# lune-v6-rev3_3.net
KiCad netlist of a schematic drawn in EasyEDA Pro
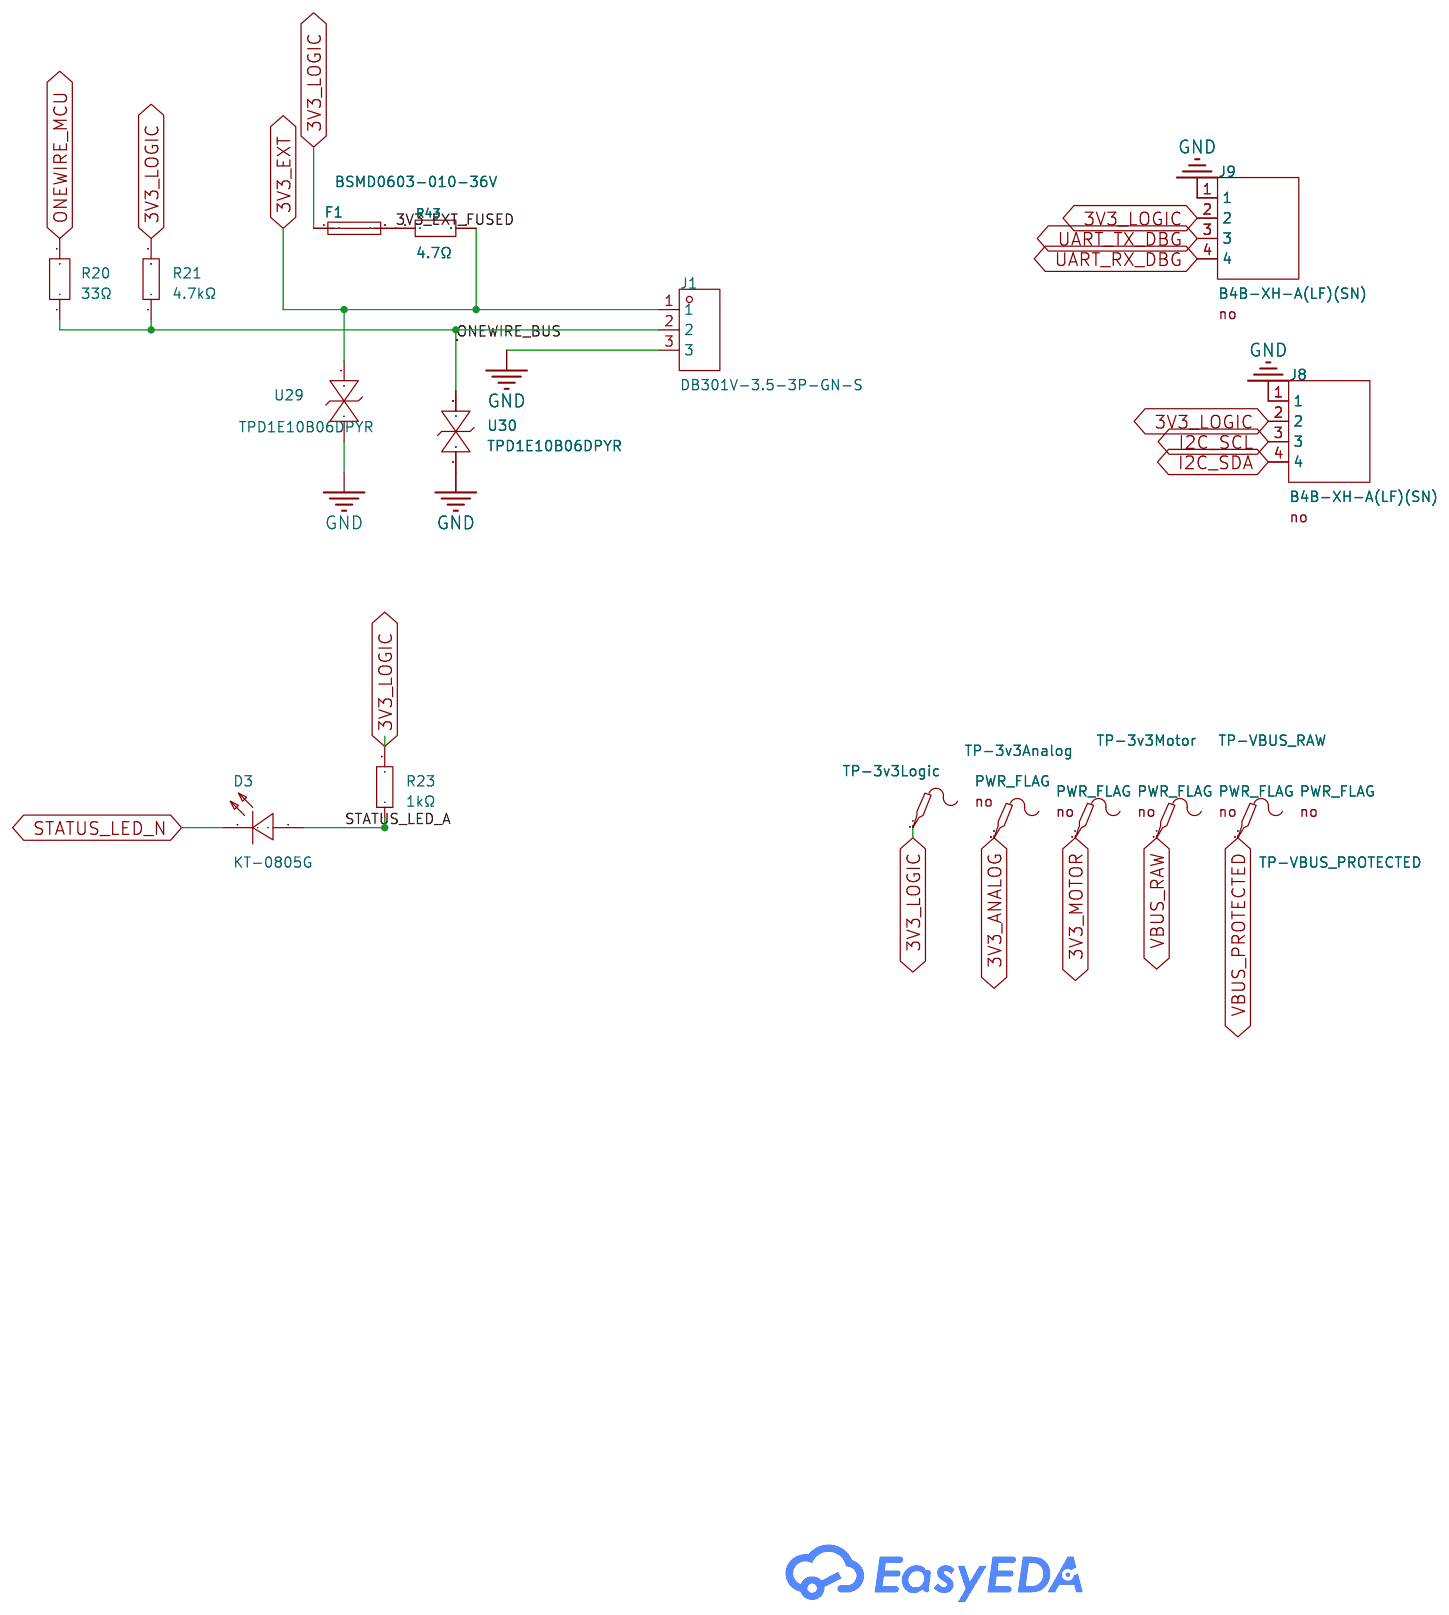
[diagram p0: Connectors]
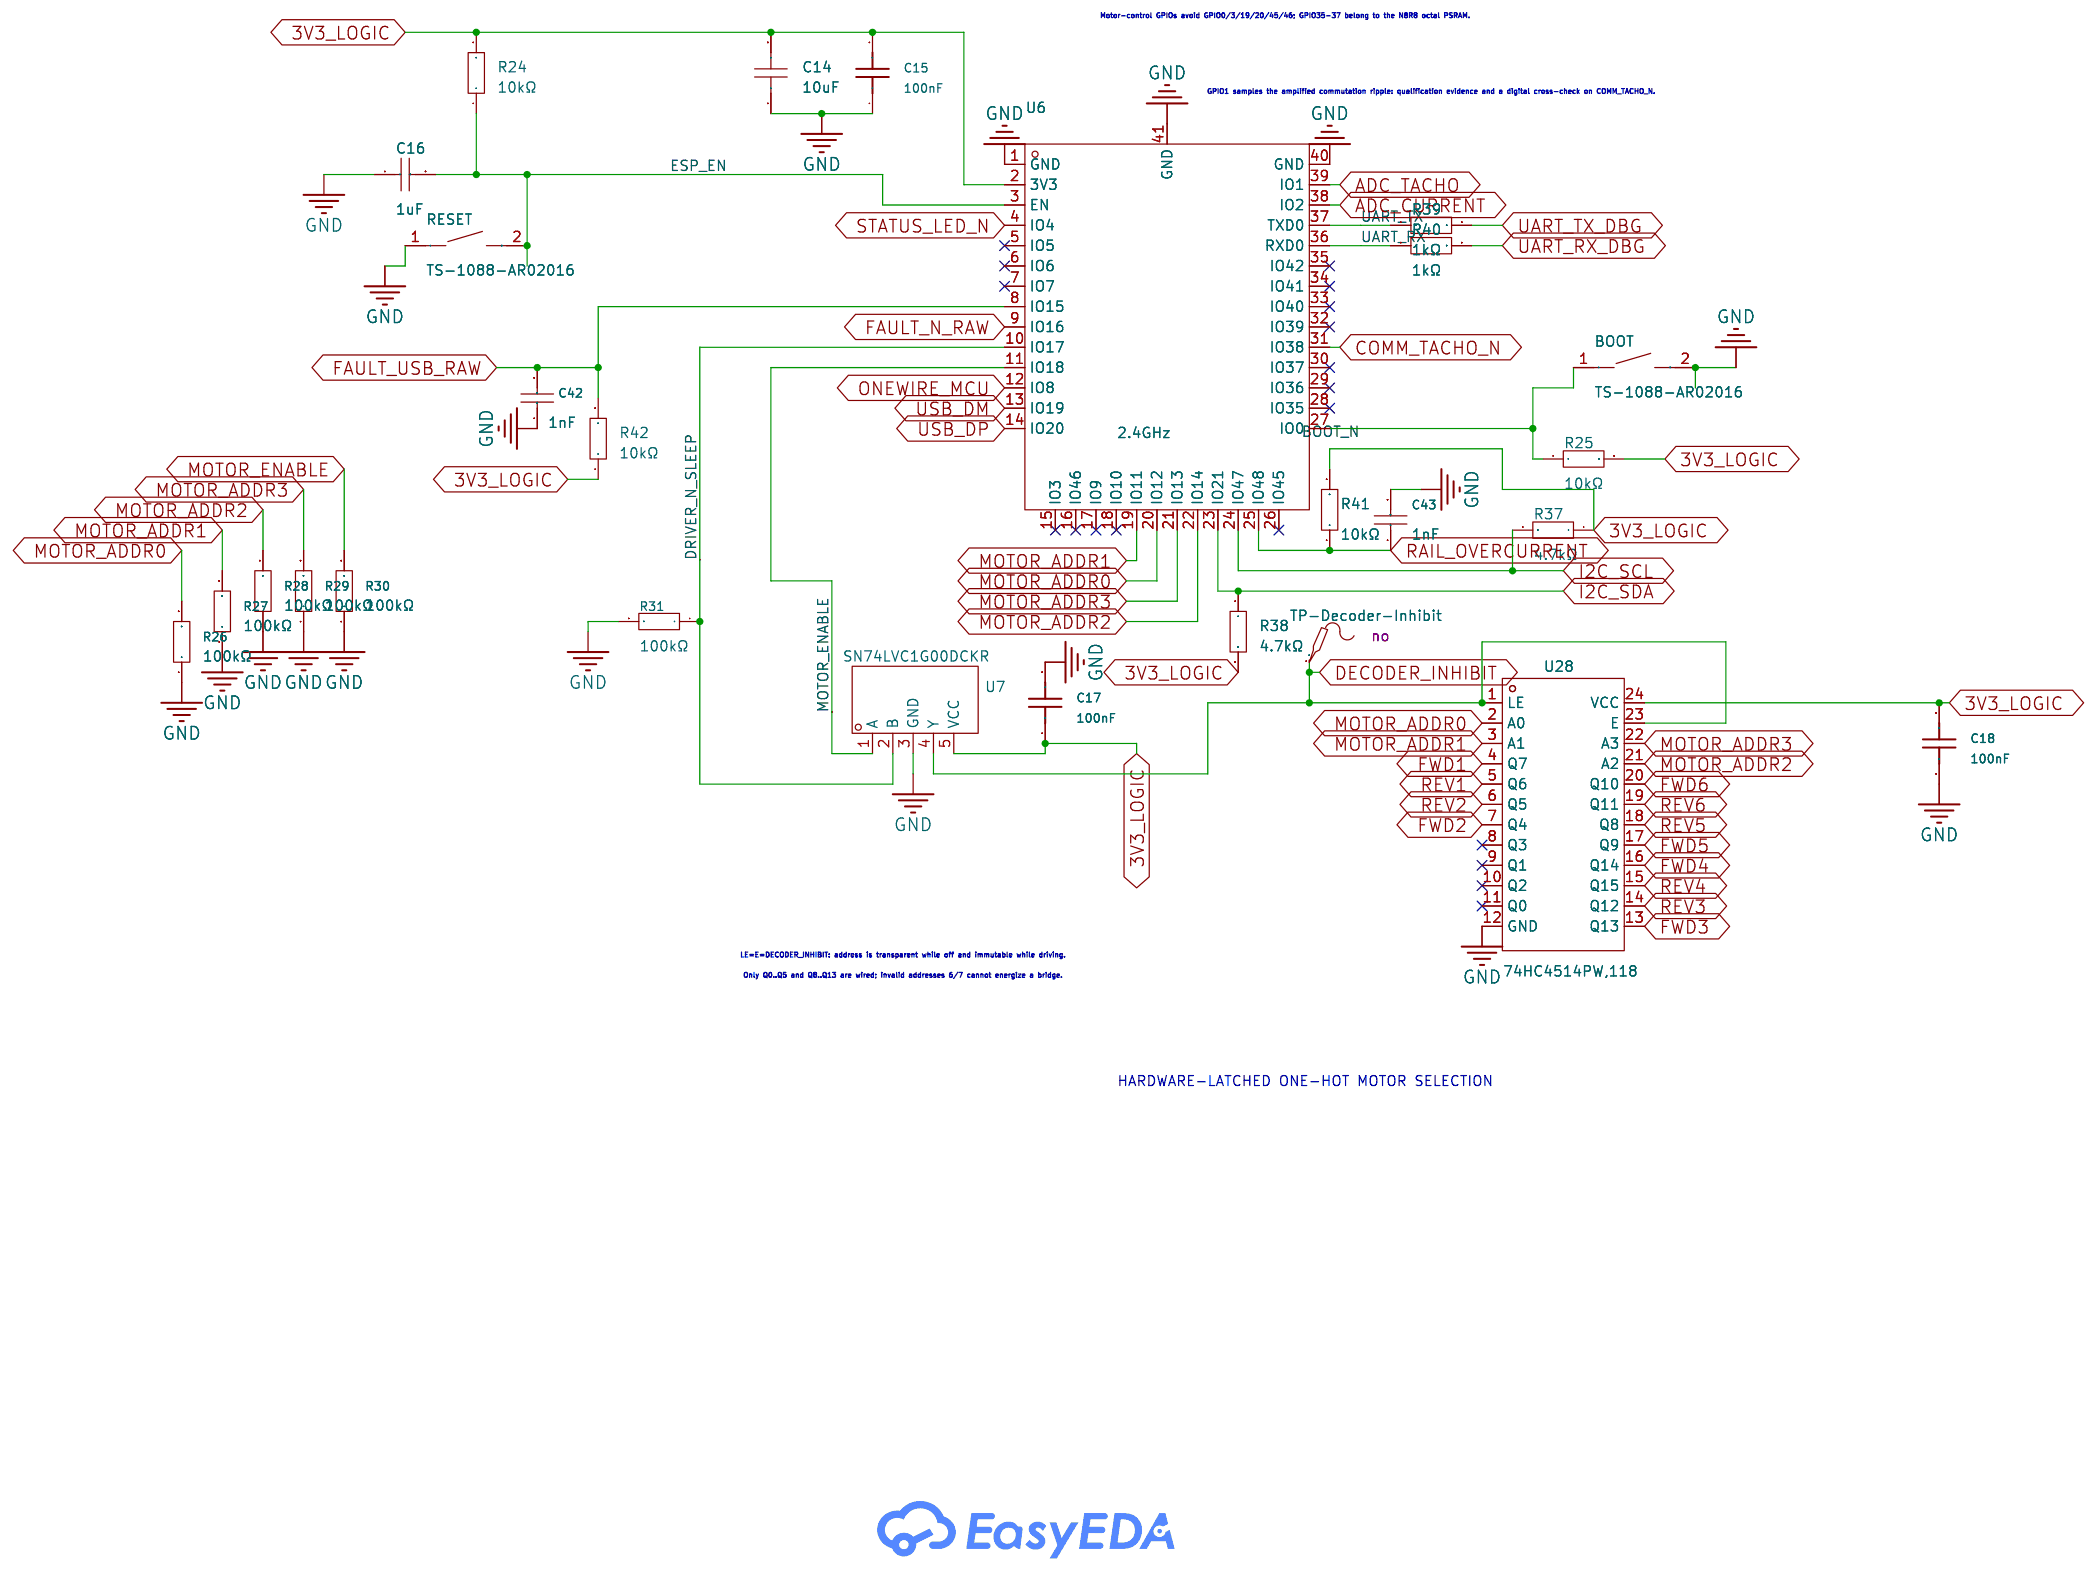
[diagram p1: Controller]
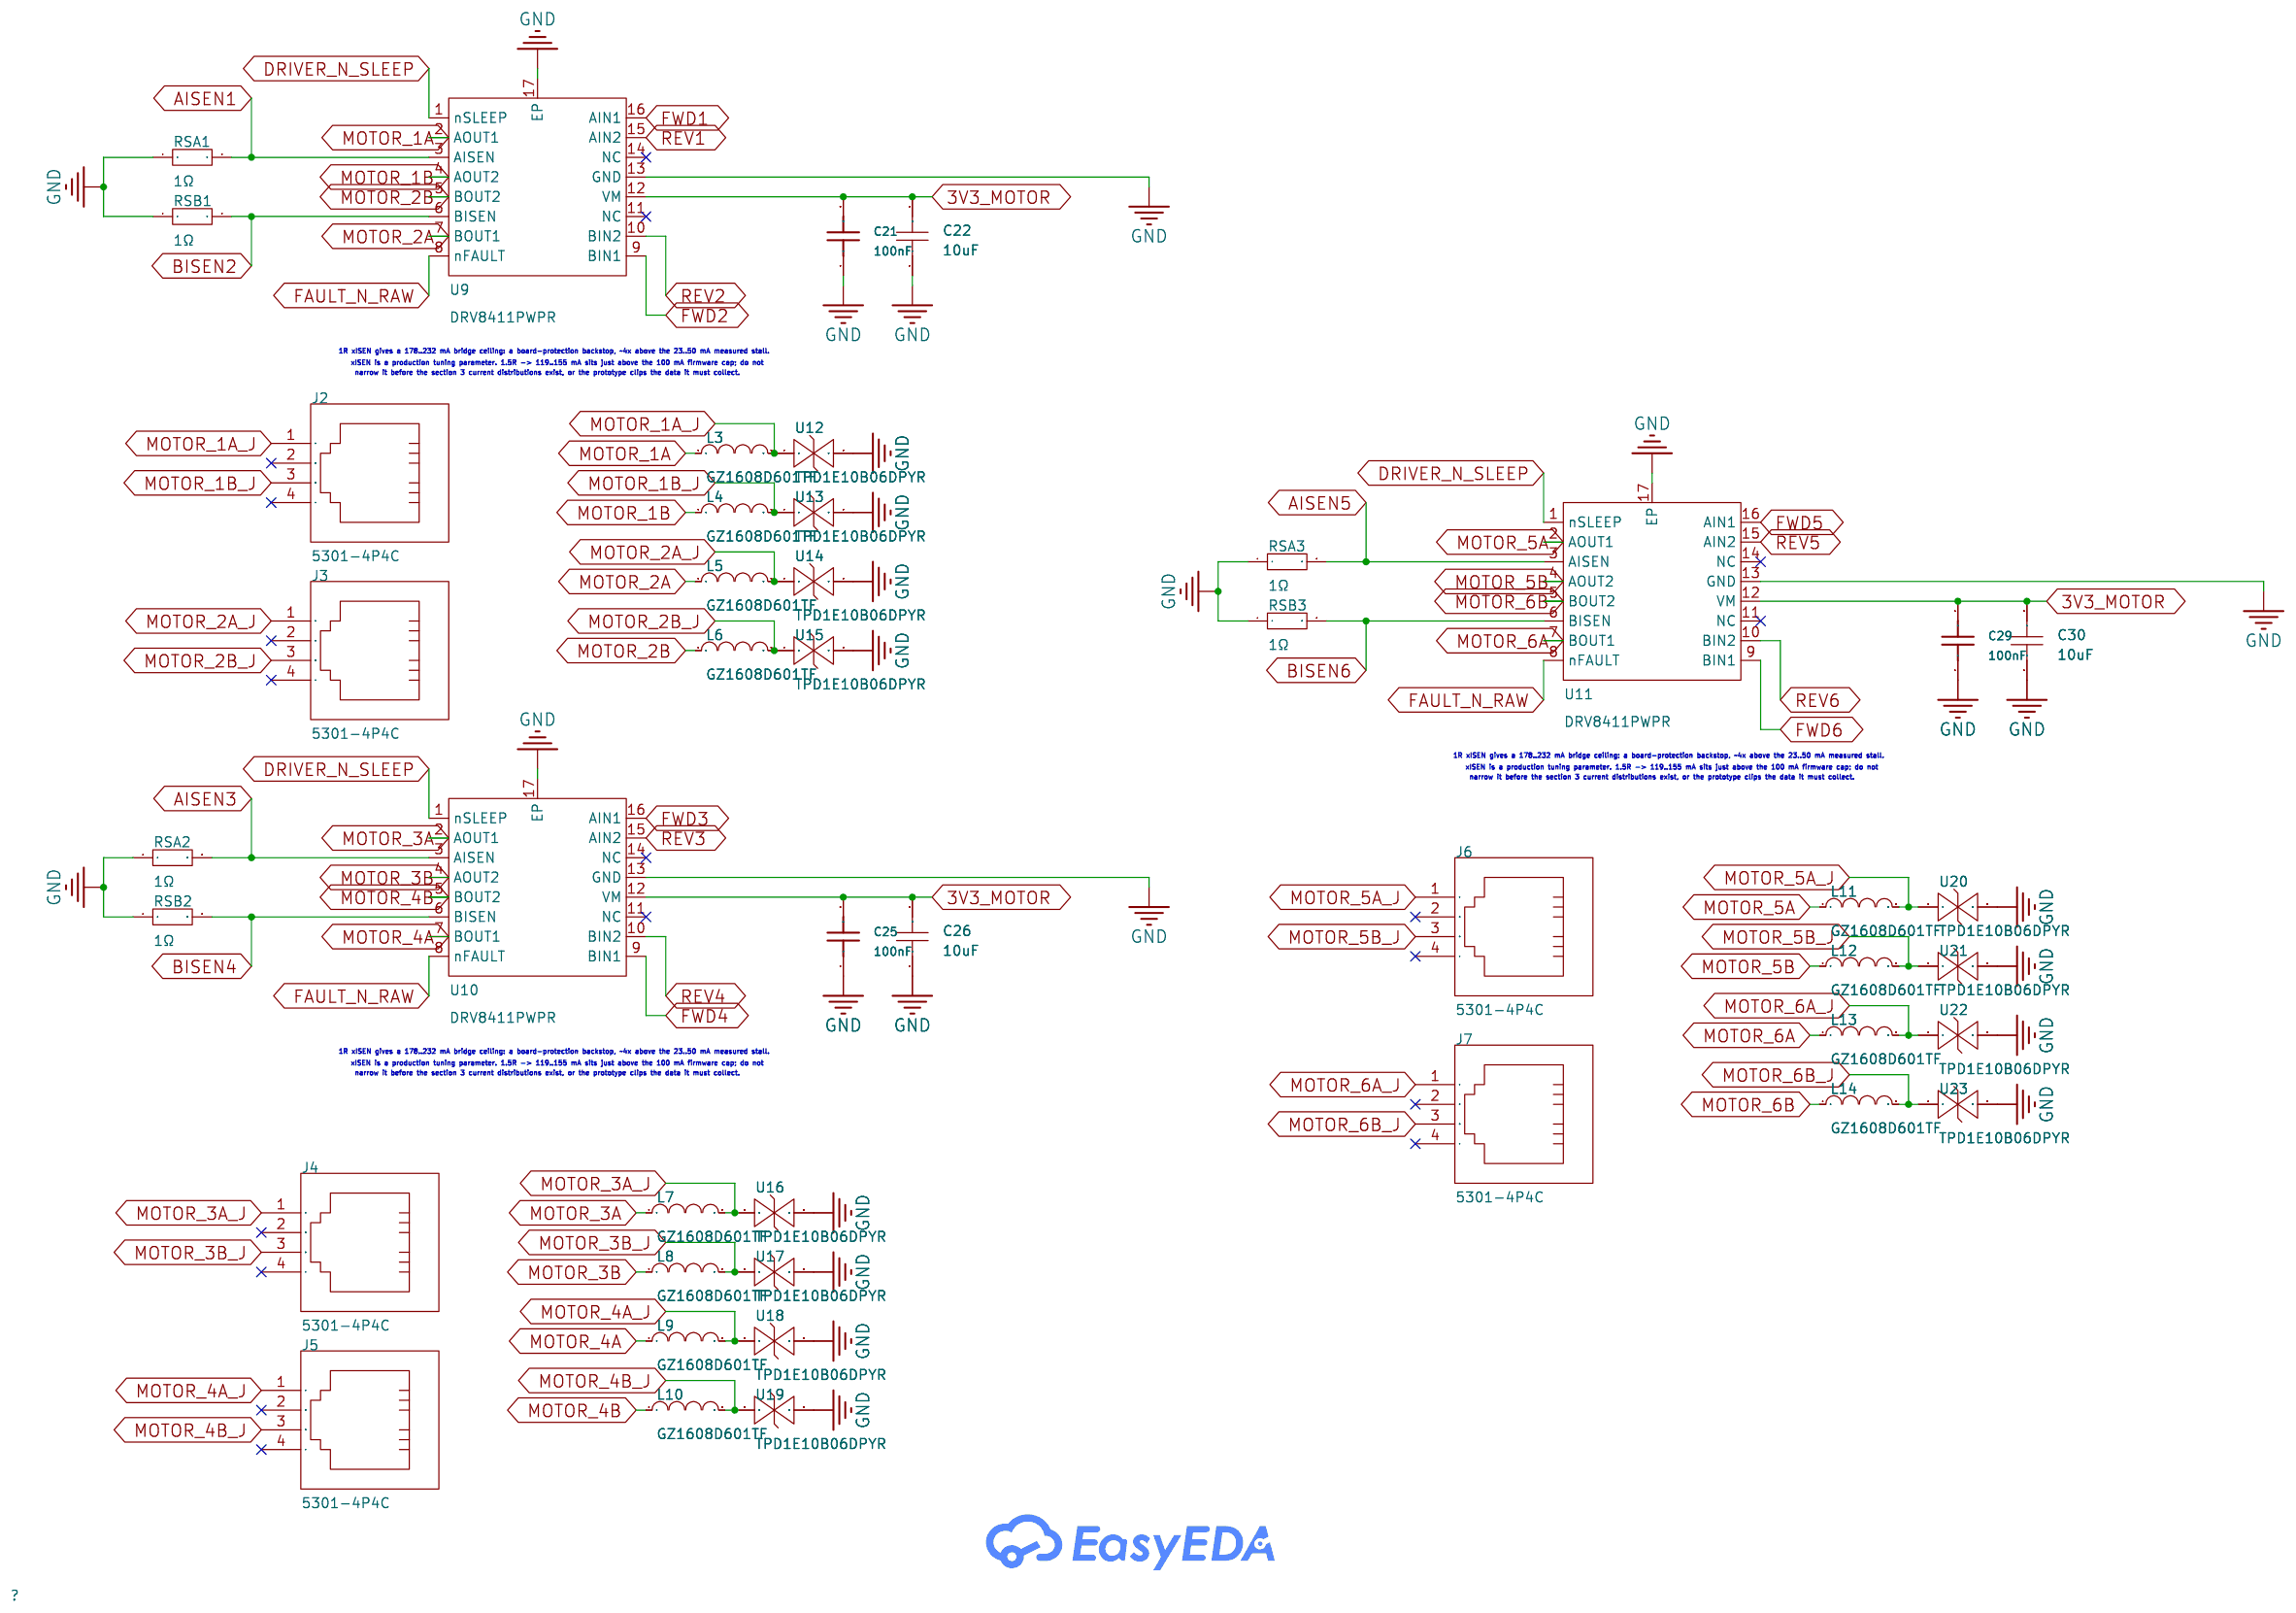
[diagram p2: Motors]
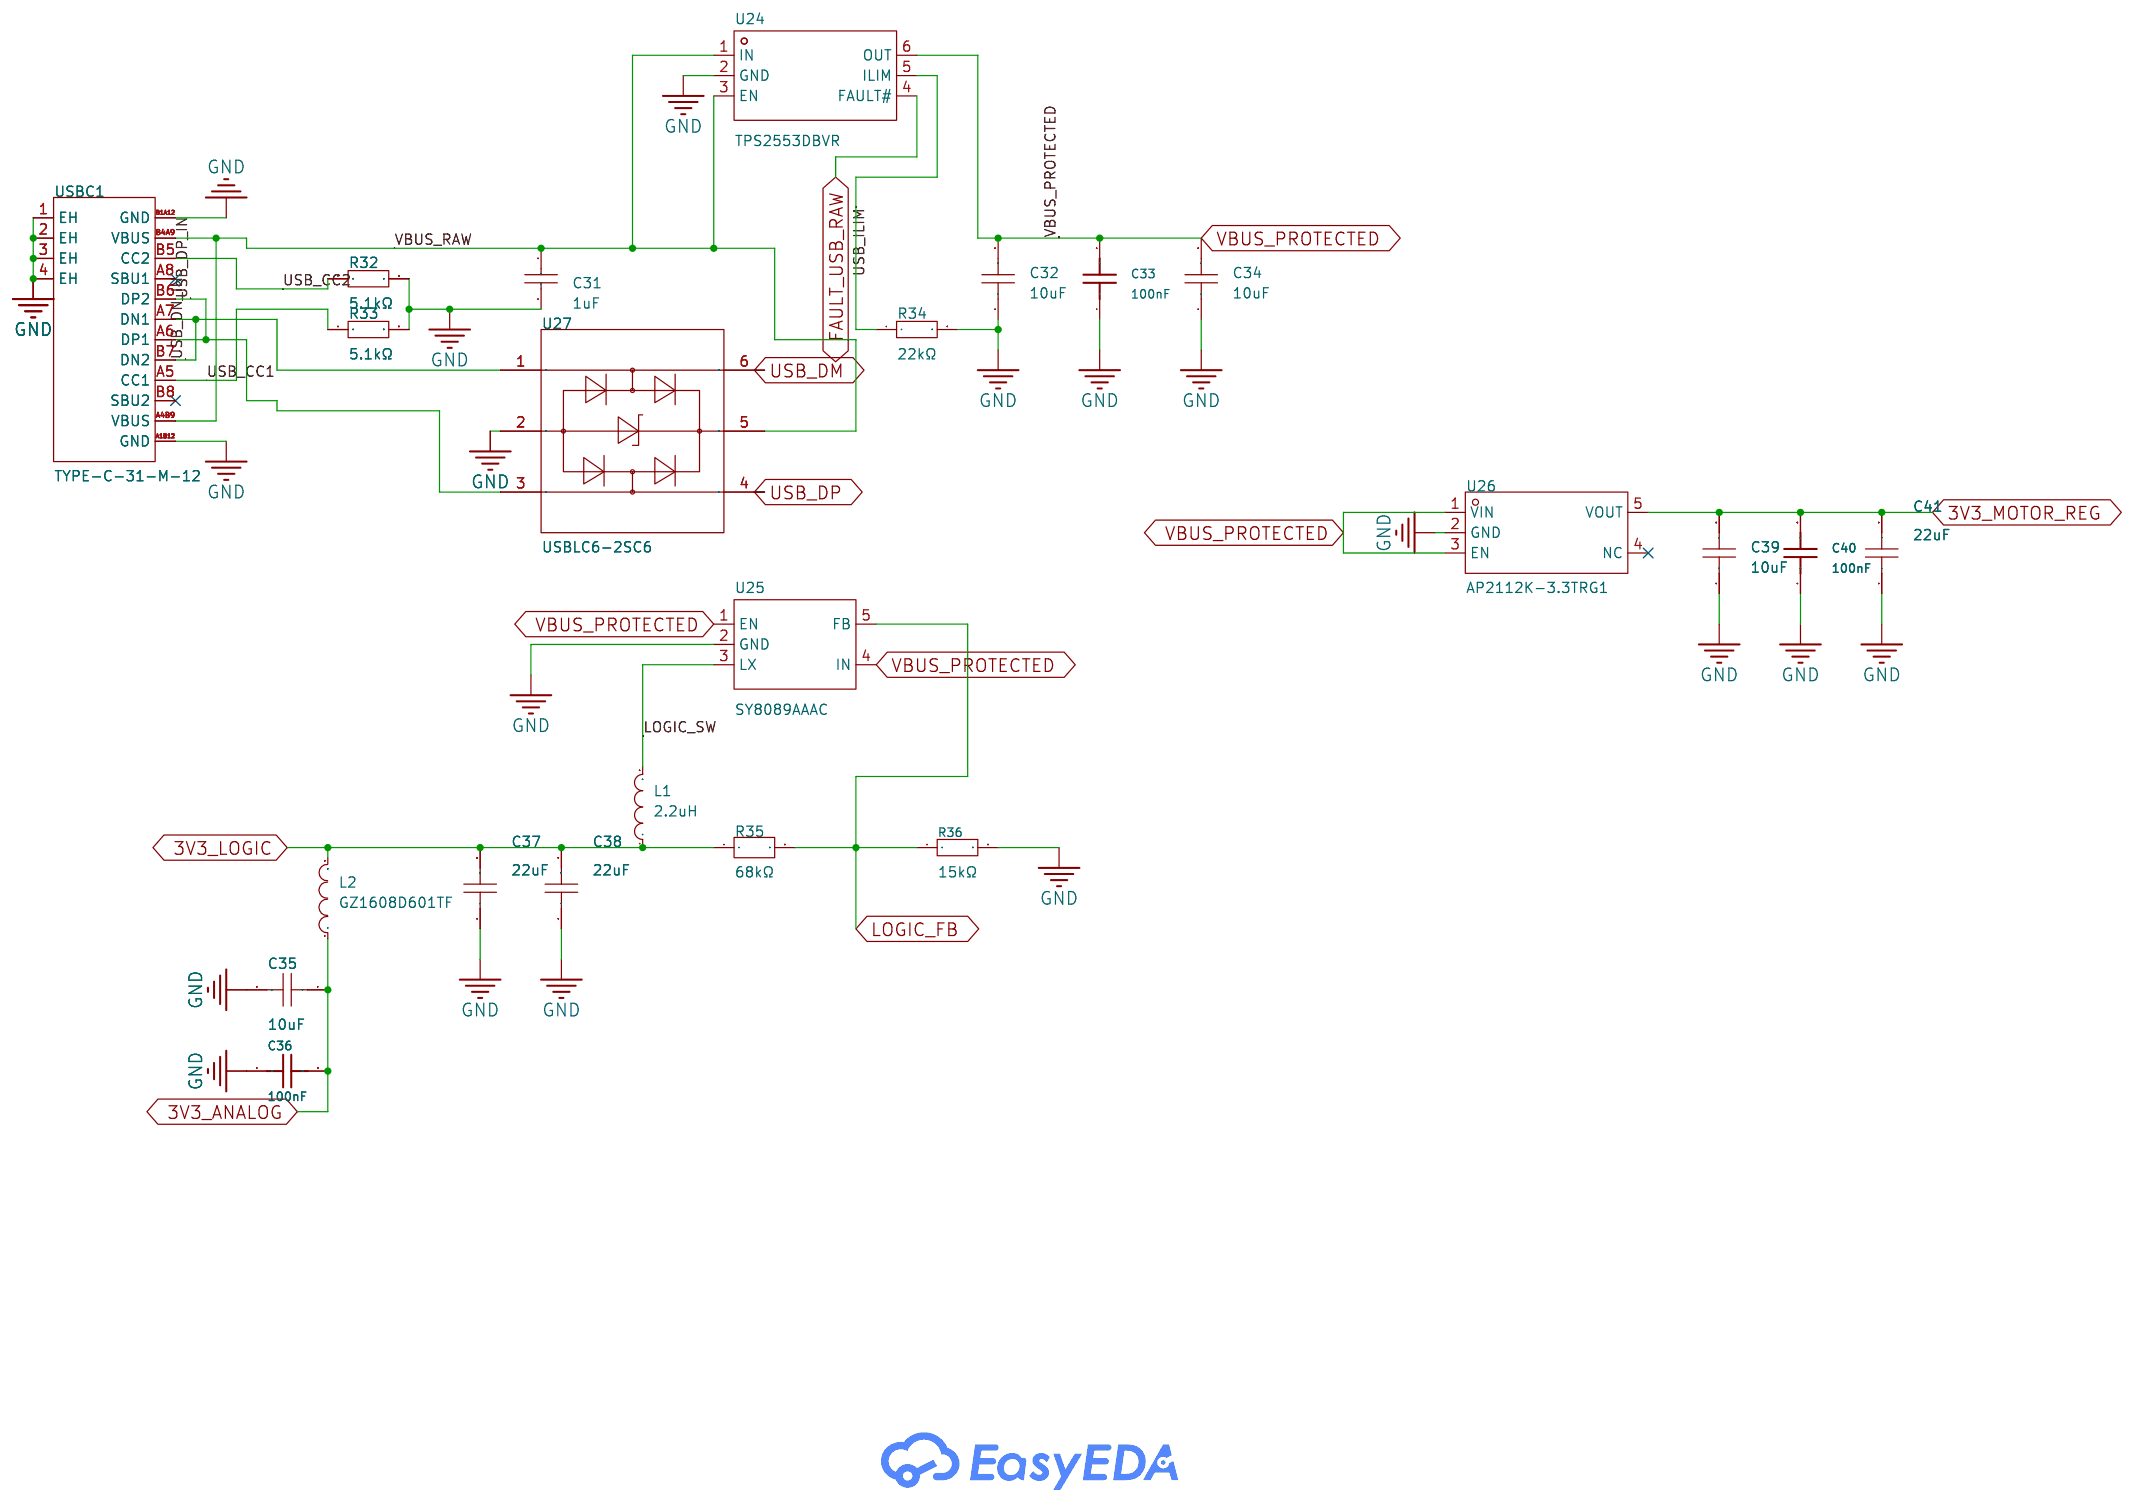
[diagram p3: Power]
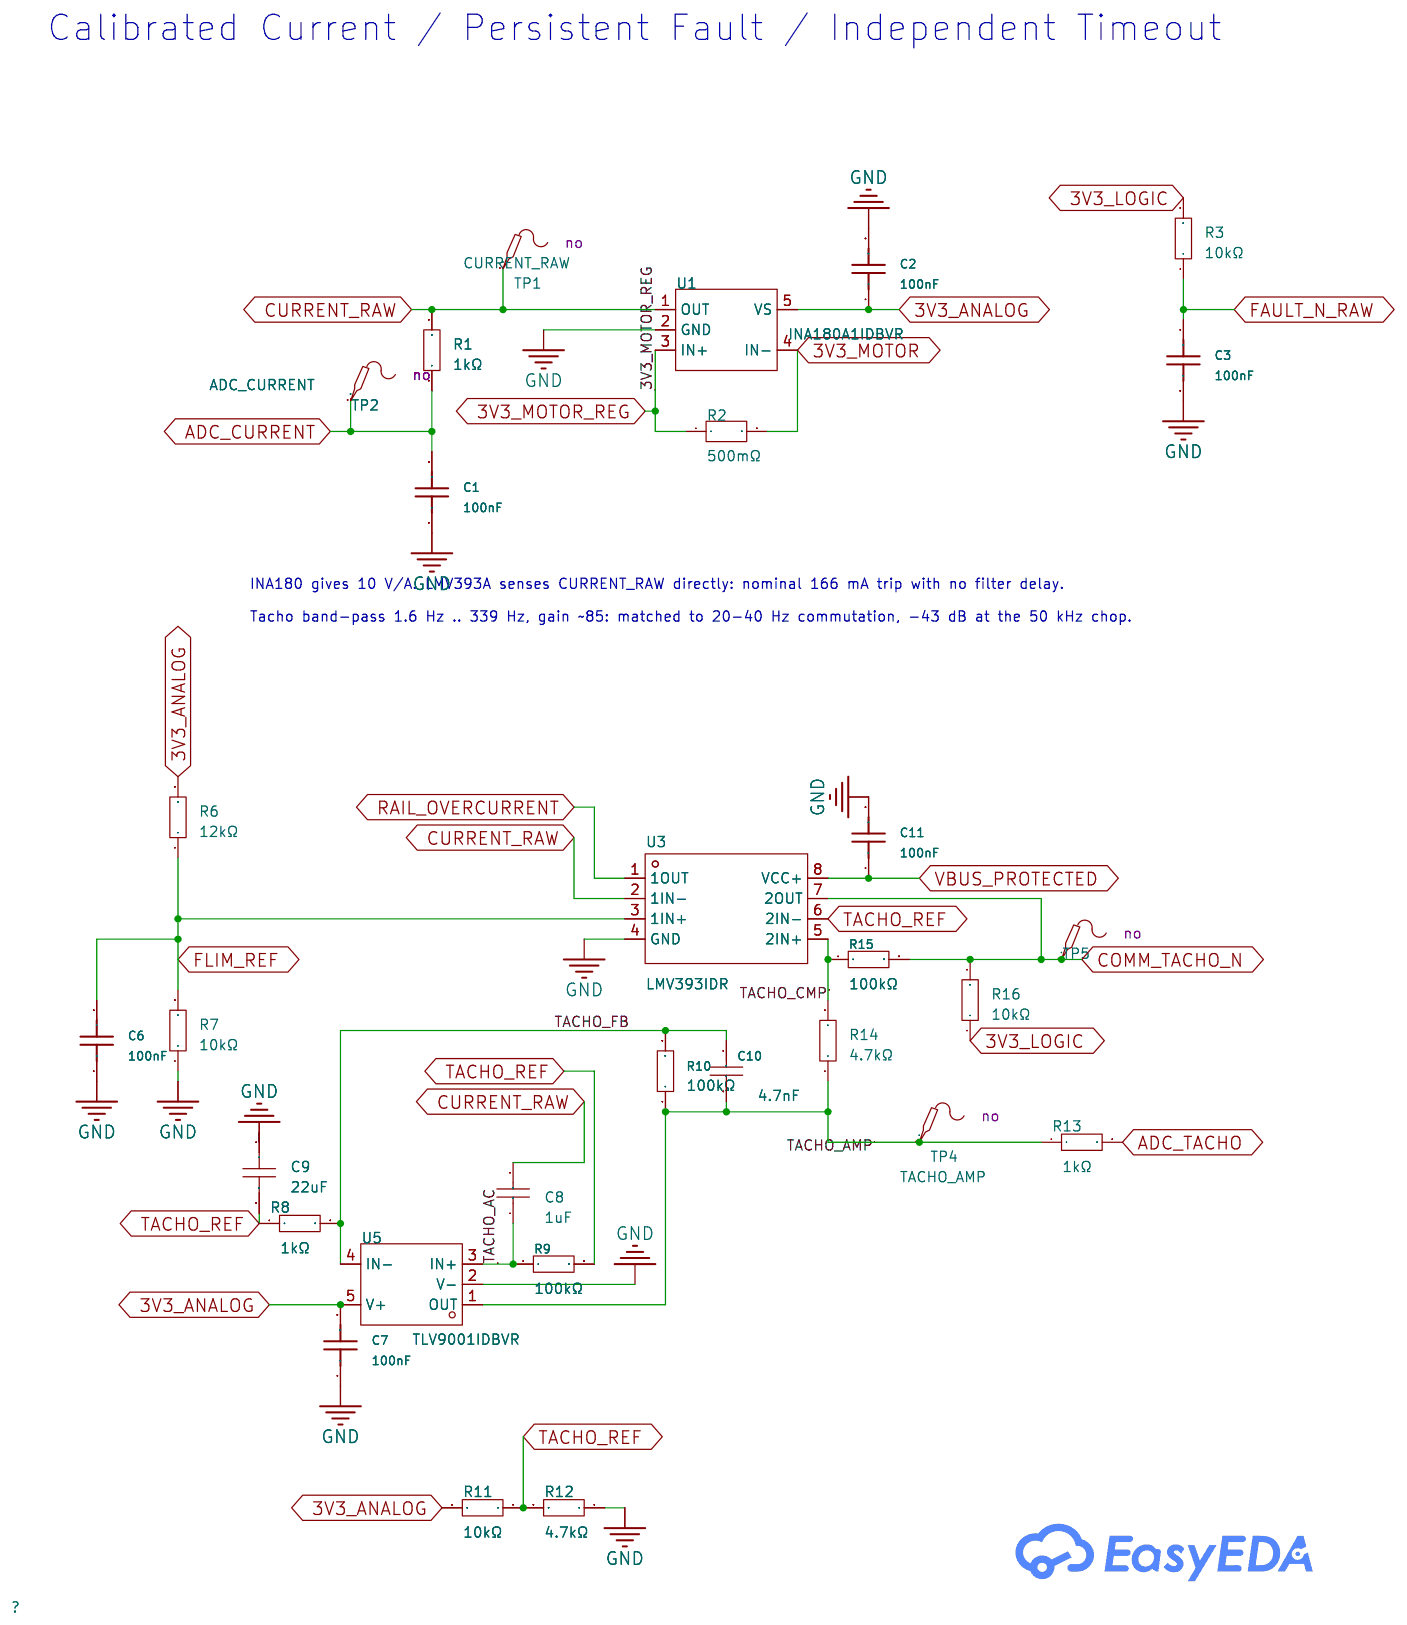
[diagram p4: Analog]

(export (version "E")
  (design (tool "Eeschema 10.0.6"))
  (components
    (comp (ref "D3")
      (value "KT-0805G")
      (footprint "easyedapro:LED0805-R-RD")
      (fields (field (name "Manufacturer") "KENTO"))
      (libsource (lib "easyedapro") (part "0805G (Green)"))
    )
    (comp (ref "F1")
      (value "BSMD0603-010-36V")
      (footprint "easyedapro:F0603")
      (fields (field (name "Manufacturer") "BHFUSE(佰宏)"))
      (libsource (lib "easyedapro") (part "BSMD0603-010-36V"))
    )
    (comp (ref "J1")
      (value "DB301V-3.5-3P-GN-S")
      (footprint "easyedapro:CONN-TH_DB301V-3.5-3P-GN")
      (fields (field (name "Manufacturer") "DORABO(地博电气)"))
      (libsource (lib "easyedapro") (part "DB301V-3.5-3P-GN"))
    )
    (comp (ref "J8")
      (value "B4B-XH-A(LF)(SN)")
      (footprint "easyedapro:CONN-TH_B4B-XH-A-LF-SN")
      (fields (field (name "Manufacturer") "JST") (field (name "Add into BOM") "no"))
      (libsource (lib "easyedapro") (part "B4B-XH-A(LF)(SN)"))
    )
    (comp (ref "J9")
      (value "B4B-XH-A(LF)(SN)")
      (footprint "easyedapro:CONN-TH_B4B-XH-A-LF-SN")
      (fields (field (name "Manufacturer") "JST") (field (name "Add into BOM") "no"))
      (libsource (lib "easyedapro") (part "B4B-XH-A(LF)(SN)"))
    )
    (comp (ref "R20")
      (value "33Ω")
      (footprint "easyedapro:R0603")
      (fields
        (field (name "Manufacturer Part") "0603WAF330JT5E")
        (field (name "Manufacturer") "UNI-ROYAL(厚声)")
      )
      (libsource (lib "easyedapro") (part "CRCW060333R0FKEA"))
    )
    (comp (ref "R21")
      (value "4.7kΩ")
      (footprint "easyedapro:R0603")
      (fields
        (field (name "Manufacturer Part") "0603WAF4701T5E")
        (field (name "Manufacturer") "UNI-ROYAL(厚声)")
      )
      (libsource (lib "easyedapro") (part "RC0603FR-074K7L"))
    )
    (comp (ref "R23")
      (value "1kΩ")
      (footprint "easyedapro:R0603")
      (fields
        (field (name "Manufacturer Part") "0603WAF1001T5E")
        (field (name "Manufacturer") "UNI-ROYAL(厚声)")
      )
      (libsource (lib "easyedapro") (part "RC0603FR-071KL"))
    )
    (comp (ref "R43")
      (value "4.7Ω")
      (footprint "easyedapro:R0603")
      (fields
        (field (name "Manufacturer Part") "0603WAF470KT5E")
        (field (name "Manufacturer") "UNI-ROYAL(厚声)")
      )
      (libsource (lib "easyedapro") (part "0603WAF470KT5E"))
    )
    (comp (ref "TP-3v3Analog")
      (value "PWR_FLAG")
      (footprint "easyedapro:Test-Point-0.5mm")
      (description "Test Point 测试点")
      (fields (field (name "Add into BOM") "no"))
      (libsource (lib "easyedapro") (part "Test-Point"))
    )
    (comp (ref "TP-3v3Logic")
      (value "PWR_FLAG")
      (footprint "easyedapro:Test-Point-0.5mm")
      (description "Test Point 测试点")
      (fields (field (name "Add into BOM") "no"))
      (libsource (lib "easyedapro") (part "Test-Point"))
    )
    (comp (ref "TP-3v3Motor")
      (value "PWR_FLAG")
      (footprint "easyedapro:Test-Point-0.5mm")
      (description "Test Point 测试点")
      (fields (field (name "Add into BOM") "no"))
      (libsource (lib "easyedapro") (part "Test-Point"))
    )
    (comp (ref "TP-VBUS_PROTECTED")
      (value "PWR_FLAG")
      (footprint "easyedapro:Test-Point-0.5mm")
      (description "Test Point 测试点")
      (fields (field (name "Add into BOM") "no"))
      (libsource (lib "easyedapro") (part "Test-Point"))
    )
    (comp (ref "TP-VBUS_RAW")
      (value "PWR_FLAG")
      (footprint "easyedapro:Test-Point-0.5mm")
      (description "Test Point 测试点")
      (fields (field (name "Add into BOM") "no"))
      (libsource (lib "easyedapro") (part "Test-Point"))
    )
    (comp (ref "U29")
      (value "TPD1E10B06DPYR")
      (footprint "easyedapro:X1SON-2_L1.0-W0.6-P0.65-BI-1")
      (fields (field (name "Manufacturer") "TI(德州仪器)"))
      (libsource (lib "easyedapro") (part "TPD1E10B06DPYR"))
    )
    (comp (ref "U30")
      (value "TPD1E10B06DPYR")
      (footprint "easyedapro:X1SON-2_L1.0-W0.6-P0.65-BI-1")
      (fields (field (name "Manufacturer") "TI(德州仪器)"))
      (libsource (lib "easyedapro") (part "TPD1E10B06DPYR"))
    )
    (comp (ref "BOOT")
      (value "TS-1088-AR02016")
      (footprint "easyedapro:SW-SMD_L3.9-W3.0-P4.45")
      (fields (field (name "Manufacturer") "XUNPU(讯普)"))
      (libsource (lib "easyedapro") (part "TS-1088-AR02016"))
    )
    (comp (ref "C14")
      (value "10uF")
      (footprint "easyedapro:C0603")
      (description "Capacitance:10uF Tolerance:±10% Tolerance:±10% Voltage Rating:16V Temperature Coefficient:X5R")
      (fields
        (field (name "Manufacturer Part") "CL10A106KP8NNNC")
        (field (name "Manufacturer") "SAMSUNG(三星)")
      )
      (libsource (lib "easyedapro") (part "TCC0603X5R106K160CT"))
    )
    (comp (ref "C15")
      (value "100nF")
      (footprint "easyedapro:C0603")
      (description "Capacitance:100nF Tolerance:±10% Tolerance:±10% Voltage Rating:50V Temperature Coefficient:X7R")
      (fields
        (field (name "Manufacturer Part") "CC0603KRX7R9BB104")
        (field (name "Manufacturer") "YAGEO(国巨)")
      )
      (libsource (lib "easyedapro") (part "CC0603KRX7R9BB104"))
    )
    (comp (ref "C16")
      (value "1uF")
      (footprint "easyedapro:C0603")
      (fields
        (field (name "Manufacturer Part") "CL10A105KB8NNNC")
        (field (name "Manufacturer") "SAMSUNG(三星)")
      )
      (libsource (lib "easyedapro") (part "0603B105K160"))
    )
    (comp (ref "C17")
      (value "100nF")
      (footprint "easyedapro:C0603")
      (description "Capacitance:100nF Tolerance:±10% Tolerance:±10% Voltage Rating:50V Temperature Coefficient:X7R")
      (fields
        (field (name "Manufacturer Part") "CC0603KRX7R9BB104")
        (field (name "Manufacturer") "YAGEO(国巨)")
      )
      (libsource (lib "easyedapro") (part "CC0603KRX7R9BB104"))
    )
    (comp (ref "C18")
      (value "100nF")
      (footprint "easyedapro:C0603")
      (description "Capacitance:100nF Tolerance:±10% Tolerance:±10% Voltage Rating:50V Temperature Coefficient:X7R")
      (fields
        (field (name "Manufacturer Part") "CC0603KRX7R9BB104")
        (field (name "Manufacturer") "YAGEO(国巨)")
      )
      (libsource (lib "easyedapro") (part "CC0603KRX7R9BB104"))
    )
    (comp (ref "C42")
      (value "1nF")
      (footprint "easyedapro:C0603")
      (fields
        (field (name "Manufacturer Part") "CL10B102KB8NNNC")
        (field (name "Manufacturer") "SAMSUNG(三星)")
      )
      (libsource (lib "easyedapro") (part "CL10B102KB8NNNC"))
    )
    (comp (ref "C43")
      (value "1nF")
      (footprint "easyedapro:C0603")
      (fields
        (field (name "Manufacturer Part") "CL10B102KB8NNNC")
        (field (name "Manufacturer") "SAMSUNG(三星)")
      )
      (libsource (lib "easyedapro") (part "CL10B102KB8NNNC"))
    )
    (comp (ref "R24")
      (value "10kΩ")
      (footprint "easyedapro:R0603")
      (fields
        (field (name "Manufacturer Part") "0603WAF1002T5E")
        (field (name "Manufacturer") "UNI-ROYAL(厚声)")
      )
      (libsource (lib "easyedapro") (part "RC0603FR-0710KL"))
    )
    (comp (ref "R25")
      (value "10kΩ")
      (footprint "easyedapro:R0603")
      (fields
        (field (name "Manufacturer Part") "0603WAF1002T5E")
        (field (name "Manufacturer") "UNI-ROYAL(厚声)")
      )
      (libsource (lib "easyedapro") (part "RC0603FR-0710KL"))
    )
    (comp (ref "R26")
      (value "100kΩ")
      (footprint "easyedapro:R0603")
      (fields
        (field (name "Manufacturer Part") "0603WAF1003T5E")
        (field (name "Manufacturer") "UNI-ROYAL(厚声)")
      )
      (libsource (lib "easyedapro") (part "RC0603FR-07100KL"))
    )
    (comp (ref "R27")
      (value "100kΩ")
      (footprint "easyedapro:R0603")
      (fields
        (field (name "Manufacturer Part") "0603WAF1003T5E")
        (field (name "Manufacturer") "UNI-ROYAL(厚声)")
      )
      (libsource (lib "easyedapro") (part "RC0603FR-07100KL"))
    )
    (comp (ref "R28")
      (value "100kΩ")
      (footprint "easyedapro:R0603")
      (fields
        (field (name "Manufacturer Part") "0603WAF1003T5E")
        (field (name "Manufacturer") "UNI-ROYAL(厚声)")
      )
      (libsource (lib "easyedapro") (part "RC0603FR-07100KL"))
    )
    (comp (ref "R29")
      (value "100kΩ")
      (footprint "easyedapro:R0603")
      (fields
        (field (name "Manufacturer Part") "0603WAF1003T5E")
        (field (name "Manufacturer") "UNI-ROYAL(厚声)")
      )
      (libsource (lib "easyedapro") (part "RC0603FR-07100KL"))
    )
    (comp (ref "R30")
      (value "100kΩ")
      (footprint "easyedapro:R0603")
      (fields
        (field (name "Manufacturer Part") "0603WAF1003T5E")
        (field (name "Manufacturer") "UNI-ROYAL(厚声)")
      )
      (libsource (lib "easyedapro") (part "RC0603FR-07100KL"))
    )
    (comp (ref "R31")
      (value "100kΩ")
      (footprint "easyedapro:R0603")
      (fields
        (field (name "Manufacturer Part") "0603WAF1003T5E")
        (field (name "Manufacturer") "UNI-ROYAL(厚声)")
      )
      (libsource (lib "easyedapro") (part "RC0603FR-07100KL"))
    )
    (comp (ref "R37")
      (value "4.7kΩ")
      (footprint "easyedapro:R0603")
      (fields
        (field (name "Manufacturer Part") "0603WAF4701T5E")
        (field (name "Manufacturer") "UNI-ROYAL(厚声)")
      )
      (libsource (lib "easyedapro") (part "RC0603FR-074K7L"))
    )
    (comp (ref "R38")
      (value "4.7kΩ")
      (footprint "easyedapro:R0603")
      (fields
        (field (name "Manufacturer Part") "0603WAF4701T5E")
        (field (name "Manufacturer") "UNI-ROYAL(厚声)")
      )
      (libsource (lib "easyedapro") (part "RC0603FR-074K7L"))
    )
    (comp (ref "R39")
      (value "1kΩ")
      (footprint "easyedapro:R0603")
      (fields
        (field (name "Manufacturer Part") "0603WAF1001T5E")
        (field (name "Manufacturer") "UNI-ROYAL(厚声)")
      )
      (libsource (lib "easyedapro") (part "RC0603FR-071KL"))
    )
    (comp (ref "R40")
      (value "1kΩ")
      (footprint "easyedapro:R0603")
      (fields
        (field (name "Manufacturer Part") "0603WAF1001T5E")
        (field (name "Manufacturer") "UNI-ROYAL(厚声)")
      )
      (libsource (lib "easyedapro") (part "RC0603FR-071KL"))
    )
    (comp (ref "R41")
      (value "10kΩ")
      (footprint "easyedapro:R0603")
      (fields
        (field (name "Manufacturer Part") "0603WAF1002T5E")
        (field (name "Manufacturer") "UNI-ROYAL(厚声)")
      )
      (libsource (lib "easyedapro") (part "RC0603FR-0710KL"))
    )
    (comp (ref "R42")
      (value "10kΩ")
      (footprint "easyedapro:R0603")
      (fields
        (field (name "Manufacturer Part") "0603WAF1002T5E")
        (field (name "Manufacturer") "UNI-ROYAL(厚声)")
      )
      (libsource (lib "easyedapro") (part "RC0603FR-0710KL"))
    )
    (comp (ref "RESET")
      (value "TS-1088-AR02016")
      (footprint "easyedapro:SW-SMD_L3.9-W3.0-P4.45")
      (fields (field (name "Manufacturer") "XUNPU(讯普)"))
      (libsource (lib "easyedapro") (part "TS-1088-AR02016"))
    )
    (comp (ref "TP-Decoder-Inhibit")
      (value "~")
      (footprint "easyedapro:Test-Point-0.5mm")
      (description "Test Point 测试点")
      (fields (field (name "Add into BOM") "no"))
      (libsource (lib "easyedapro") (part "Test-Point"))
    )
    (comp (ref "U6")
      (value "2.4GHz")
      (footprint "easyedapro:WIRELM-SMD_ESP32-S3-WROOM-1")
      (fields
        (field (name "Manufacturer Part") "ESP32-S3-WROOM-1-N8R8")
        (field (name "Manufacturer") "ESPRESSIF(乐鑫)")
      )
      (libsource (lib "easyedapro") (part "ESP32-S3-WROOM-1(N8R8)"))
    )
    (comp (ref "U7")
      (value "SN74LVC1G00DCKR")
      (footprint "easyedapro:SOT-353_L2.1-W1.3-P0.65-LS2.3-BR")
      (fields (field (name "Manufacturer") "TI(德州仪器)"))
      (libsource (lib "easyedapro") (part "SN74LVC1G00DCKR"))
    )
    (comp (ref "U28")
      (value "74HC4514PW,118")
      (footprint "easyedapro:TSSOP-24_L7.8-W4.4-P0.65-LS6.4-BL")
      (fields (field (name "Manufacturer") "Nexperia(安世)"))
      (libsource (lib "easyedapro") (part "74HC4514PW,118"))
    )
    (comp (ref "C21")
      (value "100nF")
      (footprint "easyedapro:C0603")
      (description "Capacitance:100nF Tolerance:±10% Tolerance:±10% Voltage Rating:50V Temperature Coefficient:X7R")
      (fields
        (field (name "Manufacturer Part") "CC0603KRX7R9BB104")
        (field (name "Manufacturer") "YAGEO(国巨)")
      )
      (libsource (lib "easyedapro") (part "CC0603KRX7R9BB104"))
    )
    (comp (ref "C22")
      (value "10uF")
      (footprint "easyedapro:C0603")
      (description "Capacitance:10uF Tolerance:±10% Tolerance:±10% Voltage Rating:16V Temperature Coefficient:X5R")
      (fields
        (field (name "Manufacturer Part") "CL10A106KP8NNNC")
        (field (name "Manufacturer") "SAMSUNG(三星)")
      )
      (libsource (lib "easyedapro") (part "TCC0603X5R106K160CT"))
    )
    (comp (ref "C25")
      (value "100nF")
      (footprint "easyedapro:C0603")
      (description "Capacitance:100nF Tolerance:±10% Tolerance:±10% Voltage Rating:50V Temperature Coefficient:X7R")
      (fields
        (field (name "Manufacturer Part") "CC0603KRX7R9BB104")
        (field (name "Manufacturer") "YAGEO(国巨)")
      )
      (libsource (lib "easyedapro") (part "CC0603KRX7R9BB104"))
    )
    (comp (ref "C26")
      (value "10uF")
      (footprint "easyedapro:C0603")
      (description "Capacitance:10uF Tolerance:±10% Tolerance:±10% Voltage Rating:16V Temperature Coefficient:X5R")
      (fields
        (field (name "Manufacturer Part") "CL10A106KP8NNNC")
        (field (name "Manufacturer") "SAMSUNG(三星)")
      )
      (libsource (lib "easyedapro") (part "TCC0603X5R106K160CT"))
    )
    (comp (ref "C29")
      (value "100nF")
      (footprint "easyedapro:C0603")
      (description "Capacitance:100nF Tolerance:±10% Tolerance:±10% Voltage Rating:50V Temperature Coefficient:X7R")
      (fields
        (field (name "Manufacturer Part") "CC0603KRX7R9BB104")
        (field (name "Manufacturer") "YAGEO(国巨)")
      )
      (libsource (lib "easyedapro") (part "CC0603KRX7R9BB104"))
    )
    (comp (ref "C30")
      (value "10uF")
      (footprint "easyedapro:C0603")
      (description "Capacitance:10uF Tolerance:±10% Tolerance:±10% Voltage Rating:16V Temperature Coefficient:X5R")
      (fields
        (field (name "Manufacturer Part") "CL10A106KP8NNNC")
        (field (name "Manufacturer") "SAMSUNG(三星)")
      )
      (libsource (lib "easyedapro") (part "TCC0603X5R106K160CT"))
    )
    (comp (ref "J2")
      (value "5301-4P4C")
      (footprint "easyedapro:RJ11-TH_RJ11-4P4C")
      (fields (field (name "Manufacturer") "EVERCOM(恒连)"))
      (libsource (lib "easyedapro") (part "5301-4P4C"))
    )
    (comp (ref "J3")
      (value "5301-4P4C")
      (footprint "easyedapro:RJ11-TH_RJ11-4P4C")
      (fields (field (name "Manufacturer") "EVERCOM(恒连)"))
      (libsource (lib "easyedapro") (part "5301-4P4C"))
    )
    (comp (ref "J4")
      (value "5301-4P4C")
      (footprint "easyedapro:RJ11-TH_RJ11-4P4C")
      (fields (field (name "Manufacturer") "EVERCOM(恒连)"))
      (libsource (lib "easyedapro") (part "5301-4P4C"))
    )
    (comp (ref "J5")
      (value "5301-4P4C")
      (footprint "easyedapro:RJ11-TH_RJ11-4P4C")
      (fields (field (name "Manufacturer") "EVERCOM(恒连)"))
      (libsource (lib "easyedapro") (part "5301-4P4C"))
    )
    (comp (ref "J6")
      (value "5301-4P4C")
      (footprint "easyedapro:RJ11-TH_RJ11-4P4C")
      (fields (field (name "Manufacturer") "EVERCOM(恒连)"))
      (libsource (lib "easyedapro") (part "5301-4P4C"))
    )
    (comp (ref "J7")
      (value "5301-4P4C")
      (footprint "easyedapro:RJ11-TH_RJ11-4P4C")
      (fields (field (name "Manufacturer") "EVERCOM(恒连)"))
      (libsource (lib "easyedapro") (part "5301-4P4C"))
    )
    (comp (ref "L3")
      (value "GZ1608D601TF")
      (footprint "easyedapro:L0603")
      (fields (field (name "Manufacturer") "Sunlord(顺络)"))
      (libsource (lib "easyedapro") (part "GZ1608D601TF"))
    )
    (comp (ref "L4")
      (value "GZ1608D601TF")
      (footprint "easyedapro:L0603")
      (fields (field (name "Manufacturer") "Sunlord(顺络)"))
      (libsource (lib "easyedapro") (part "GZ1608D601TF"))
    )
    (comp (ref "L5")
      (value "GZ1608D601TF")
      (footprint "easyedapro:L0603")
      (fields (field (name "Manufacturer") "Sunlord(顺络)"))
      (libsource (lib "easyedapro") (part "GZ1608D601TF"))
    )
    (comp (ref "L6")
      (value "GZ1608D601TF")
      (footprint "easyedapro:L0603")
      (fields (field (name "Manufacturer") "Sunlord(顺络)"))
      (libsource (lib "easyedapro") (part "GZ1608D601TF"))
    )
    (comp (ref "L7")
      (value "GZ1608D601TF")
      (footprint "easyedapro:L0603")
      (fields (field (name "Manufacturer") "Sunlord(顺络)"))
      (libsource (lib "easyedapro") (part "GZ1608D601TF"))
    )
    (comp (ref "L8")
      (value "GZ1608D601TF")
      (footprint "easyedapro:L0603")
      (fields (field (name "Manufacturer") "Sunlord(顺络)"))
      (libsource (lib "easyedapro") (part "GZ1608D601TF"))
    )
    (comp (ref "L9")
      (value "GZ1608D601TF")
      (footprint "easyedapro:L0603")
      (fields (field (name "Manufacturer") "Sunlord(顺络)"))
      (libsource (lib "easyedapro") (part "GZ1608D601TF"))
    )
    (comp (ref "L10")
      (value "GZ1608D601TF")
      (footprint "easyedapro:L0603")
      (fields (field (name "Manufacturer") "Sunlord(顺络)"))
      (libsource (lib "easyedapro") (part "GZ1608D601TF"))
    )
    (comp (ref "L11")
      (value "GZ1608D601TF")
      (footprint "easyedapro:L0603")
      (fields (field (name "Manufacturer") "Sunlord(顺络)"))
      (libsource (lib "easyedapro") (part "GZ1608D601TF"))
    )
    (comp (ref "L12")
      (value "GZ1608D601TF")
      (footprint "easyedapro:L0603")
      (fields (field (name "Manufacturer") "Sunlord(顺络)"))
      (libsource (lib "easyedapro") (part "GZ1608D601TF"))
    )
    (comp (ref "L13")
      (value "GZ1608D601TF")
      (footprint "easyedapro:L0603")
      (fields (field (name "Manufacturer") "Sunlord(顺络)"))
      (libsource (lib "easyedapro") (part "GZ1608D601TF"))
    )
    (comp (ref "L14")
      (value "GZ1608D601TF")
      (footprint "easyedapro:L0603")
      (fields (field (name "Manufacturer") "Sunlord(顺络)"))
      (libsource (lib "easyedapro") (part "GZ1608D601TF"))
    )
    (comp (ref "RSA1")
      (value "1Ω")
      (footprint "easyedapro:R0603")
      (fields
        (field (name "Manufacturer Part") "0603WAF100KT5E")
        (field (name "Manufacturer") "UNI-ROYAL(厚声)")
      )
      (libsource (lib "easyedapro") (part "RC0603FR-071RL"))
    )
    (comp (ref "RSA2")
      (value "1Ω")
      (footprint "easyedapro:R0603")
      (fields
        (field (name "Manufacturer Part") "0603WAF100KT5E")
        (field (name "Manufacturer") "UNI-ROYAL(厚声)")
      )
      (libsource (lib "easyedapro") (part "RC0603FR-071RL"))
    )
    (comp (ref "RSA3")
      (value "1Ω")
      (footprint "easyedapro:R0603")
      (fields
        (field (name "Manufacturer Part") "0603WAF100KT5E")
        (field (name "Manufacturer") "UNI-ROYAL(厚声)")
      )
      (libsource (lib "easyedapro") (part "RC0603FR-071RL"))
    )
    (comp (ref "RSB1")
      (value "1Ω")
      (footprint "easyedapro:R0603")
      (fields
        (field (name "Manufacturer Part") "0603WAF100KT5E")
        (field (name "Manufacturer") "UNI-ROYAL(厚声)")
      )
      (libsource (lib "easyedapro") (part "RC0603FR-071RL"))
    )
    (comp (ref "RSB2")
      (value "1Ω")
      (footprint "easyedapro:R0603")
      (fields
        (field (name "Manufacturer Part") "0603WAF100KT5E")
        (field (name "Manufacturer") "UNI-ROYAL(厚声)")
      )
      (libsource (lib "easyedapro") (part "RC0603FR-071RL"))
    )
    (comp (ref "RSB3")
      (value "1Ω")
      (footprint "easyedapro:R0603")
      (fields
        (field (name "Manufacturer Part") "0603WAF100KT5E")
        (field (name "Manufacturer") "UNI-ROYAL(厚声)")
      )
      (libsource (lib "easyedapro") (part "RC0603FR-071RL"))
    )
    (comp (ref "U9")
      (value "DRV8411PWPR")
      (footprint "easyedapro:HTSSOP-16_L5.0-W4.4-P0.65-LS6.4-TL-EP-1")
      (fields (field (name "Manufacturer") "TI(德州仪器)"))
      (libsource (lib "easyedapro") (part "DRV8411PWPR"))
    )
    (comp (ref "U10")
      (value "DRV8411PWPR")
      (footprint "easyedapro:HTSSOP-16_L5.0-W4.4-P0.65-LS6.4-TL-EP-1")
      (fields (field (name "Manufacturer") "TI(德州仪器)"))
      (libsource (lib "easyedapro") (part "DRV8411PWPR"))
    )
    (comp (ref "U11")
      (value "DRV8411PWPR")
      (footprint "easyedapro:HTSSOP-16_L5.0-W4.4-P0.65-LS6.4-TL-EP-1")
      (fields (field (name "Manufacturer") "TI(德州仪器)"))
      (libsource (lib "easyedapro") (part "DRV8411PWPR"))
    )
    (comp (ref "U12")
      (value "TPD1E10B06DPYR")
      (footprint "easyedapro:X1SON-2_L1.0-W0.6-P0.65-BI-1")
      (fields (field (name "Manufacturer") "TI(德州仪器)"))
      (libsource (lib "easyedapro") (part "TPD1E10B06DPYR"))
    )
    (comp (ref "U13")
      (value "TPD1E10B06DPYR")
      (footprint "easyedapro:X1SON-2_L1.0-W0.6-P0.65-BI-1")
      (fields (field (name "Manufacturer") "TI(德州仪器)"))
      (libsource (lib "easyedapro") (part "TPD1E10B06DPYR"))
    )
    (comp (ref "U14")
      (value "TPD1E10B06DPYR")
      (footprint "easyedapro:X1SON-2_L1.0-W0.6-P0.65-BI-1")
      (fields (field (name "Manufacturer") "TI(德州仪器)"))
      (libsource (lib "easyedapro") (part "TPD1E10B06DPYR"))
    )
    (comp (ref "U15")
      (value "TPD1E10B06DPYR")
      (footprint "easyedapro:X1SON-2_L1.0-W0.6-P0.65-BI-1")
      (fields (field (name "Manufacturer") "TI(德州仪器)"))
      (libsource (lib "easyedapro") (part "TPD1E10B06DPYR"))
    )
    (comp (ref "U16")
      (value "TPD1E10B06DPYR")
      (footprint "easyedapro:X1SON-2_L1.0-W0.6-P0.65-BI-1")
      (fields (field (name "Manufacturer") "TI(德州仪器)"))
      (libsource (lib "easyedapro") (part "TPD1E10B06DPYR"))
    )
    (comp (ref "U17")
      (value "TPD1E10B06DPYR")
      (footprint "easyedapro:X1SON-2_L1.0-W0.6-P0.65-BI-1")
      (fields (field (name "Manufacturer") "TI(德州仪器)"))
      (libsource (lib "easyedapro") (part "TPD1E10B06DPYR"))
    )
    (comp (ref "U18")
      (value "TPD1E10B06DPYR")
      (footprint "easyedapro:X1SON-2_L1.0-W0.6-P0.65-BI-1")
      (fields (field (name "Manufacturer") "TI(德州仪器)"))
      (libsource (lib "easyedapro") (part "TPD1E10B06DPYR"))
    )
    (comp (ref "U19")
      (value "TPD1E10B06DPYR")
      (footprint "easyedapro:X1SON-2_L1.0-W0.6-P0.65-BI-1")
      (fields (field (name "Manufacturer") "TI(德州仪器)"))
      (libsource (lib "easyedapro") (part "TPD1E10B06DPYR"))
    )
    (comp (ref "U20")
      (value "TPD1E10B06DPYR")
      (footprint "easyedapro:X1SON-2_L1.0-W0.6-P0.65-BI-1")
      (fields (field (name "Manufacturer") "TI(德州仪器)"))
      (libsource (lib "easyedapro") (part "TPD1E10B06DPYR"))
    )
    (comp (ref "U21")
      (value "TPD1E10B06DPYR")
      (footprint "easyedapro:X1SON-2_L1.0-W0.6-P0.65-BI-1")
      (fields (field (name "Manufacturer") "TI(德州仪器)"))
      (libsource (lib "easyedapro") (part "TPD1E10B06DPYR"))
    )
    (comp (ref "U22")
      (value "TPD1E10B06DPYR")
      (footprint "easyedapro:X1SON-2_L1.0-W0.6-P0.65-BI-1")
      (fields (field (name "Manufacturer") "TI(德州仪器)"))
      (libsource (lib "easyedapro") (part "TPD1E10B06DPYR"))
    )
    (comp (ref "U23")
      (value "TPD1E10B06DPYR")
      (footprint "easyedapro:X1SON-2_L1.0-W0.6-P0.65-BI-1")
      (fields (field (name "Manufacturer") "TI(德州仪器)"))
      (libsource (lib "easyedapro") (part "TPD1E10B06DPYR"))
    )
    (comp (ref "C31")
      (value "1uF")
      (footprint "easyedapro:C0603")
      (fields
        (field (name "Manufacturer Part") "CL10A105KB8NNNC")
        (field (name "Manufacturer") "SAMSUNG(三星)")
      )
      (libsource (lib "easyedapro") (part "0603B105K160"))
    )
    (comp (ref "C32")
      (value "10uF")
      (footprint "easyedapro:C0603")
      (description "Capacitance:10uF Tolerance:±10% Tolerance:±10% Voltage Rating:16V Temperature Coefficient:X5R")
      (fields
        (field (name "Manufacturer Part") "CL10A106MA8NRNC")
        (field (name "Manufacturer") "SAMSUNG(三星)")
      )
      (libsource (lib "easyedapro") (part "TCC0603X5R106K160CT"))
    )
    (comp (ref "C33")
      (value "100nF")
      (footprint "easyedapro:C0603")
      (description "Capacitance:100nF Tolerance:±10% Tolerance:±10% Voltage Rating:50V Temperature Coefficient:X7R")
      (fields
        (field (name "Manufacturer Part") "CC0603KRX7R9BB104")
        (field (name "Manufacturer") "YAGEO(国巨)")
      )
      (libsource (lib "easyedapro") (part "CC0603KRX7R9BB104"))
    )
    (comp (ref "C34")
      (value "10uF")
      (footprint "easyedapro:C0603")
      (description "Capacitance:10uF Tolerance:±10% Tolerance:±10% Voltage Rating:16V Temperature Coefficient:X5R")
      (fields
        (field (name "Manufacturer Part") "CL10A106MA8NRNC")
        (field (name "Manufacturer") "SAMSUNG(三星)")
      )
      (libsource (lib "easyedapro") (part "TCC0603X5R106K160CT"))
    )
    (comp (ref "C35")
      (value "10uF")
      (footprint "easyedapro:C0603")
      (description "Capacitance:10uF Tolerance:±10% Tolerance:±10% Voltage Rating:16V Temperature Coefficient:X5R")
      (fields
        (field (name "Manufacturer Part") "CL10A106KP8NNNC")
        (field (name "Manufacturer") "SAMSUNG(三星)")
      )
      (libsource (lib "easyedapro") (part "TCC0603X5R106K160CT"))
    )
    (comp (ref "C36")
      (value "100nF")
      (footprint "easyedapro:C0603")
      (description "Capacitance:100nF Tolerance:±10% Tolerance:±10% Voltage Rating:50V Temperature Coefficient:X7R")
      (fields
        (field (name "Manufacturer Part") "CC0603KRX7R9BB104")
        (field (name "Manufacturer") "YAGEO(国巨)")
      )
      (libsource (lib "easyedapro") (part "CC0603KRX7R9BB104"))
    )
    (comp (ref "C37")
      (value "22uF")
      (footprint "easyedapro:C0805")
      (description "Capacitance:22uF Tolerance:±10% Tolerance:±10% Voltage Rating:6.3V Temperature Coefficient:X5R")
      (fields
        (field (name "Manufacturer Part") "CL21A226MAQNNNE")
        (field (name "Manufacturer") "SAMSUNG(三星)")
      )
      (libsource (lib "easyedapro") (part "TCC0805X5R226K6R3FT"))
    )
    (comp (ref "C38")
      (value "22uF")
      (footprint "easyedapro:C0805")
      (description "Capacitance:22uF Tolerance:±10% Tolerance:±10% Voltage Rating:6.3V Temperature Coefficient:X5R")
      (fields
        (field (name "Manufacturer Part") "CL21A226MAQNNNE")
        (field (name "Manufacturer") "SAMSUNG(三星)")
      )
      (libsource (lib "easyedapro") (part "TCC0805X5R226K6R3FT"))
    )
    (comp (ref "C39")
      (value "10uF")
      (footprint "easyedapro:C0603")
      (description "Capacitance:10uF Tolerance:±10% Tolerance:±10% Voltage Rating:16V Temperature Coefficient:X5R")
      (fields
        (field (name "Manufacturer Part") "CL10A106KP8NNNC")
        (field (name "Manufacturer") "SAMSUNG(三星)")
      )
      (libsource (lib "easyedapro") (part "TCC0603X5R106K160CT"))
    )
    (comp (ref "C40")
      (value "100nF")
      (footprint "easyedapro:C0603")
      (description "Capacitance:100nF Tolerance:±10% Tolerance:±10% Voltage Rating:50V Temperature Coefficient:X7R")
      (fields
        (field (name "Manufacturer Part") "CC0603KRX7R9BB104")
        (field (name "Manufacturer") "YAGEO(国巨)")
      )
      (libsource (lib "easyedapro") (part "CC0603KRX7R9BB104"))
    )
    (comp (ref "C41")
      (value "22uF")
      (footprint "easyedapro:C0805")
      (description "Capacitance:22uF Tolerance:±10% Tolerance:±10% Voltage Rating:6.3V Temperature Coefficient:X5R")
      (fields
        (field (name "Manufacturer Part") "CL21A226MAQNNNE")
        (field (name "Manufacturer") "SAMSUNG(三星)")
      )
      (libsource (lib "easyedapro") (part "TCC0805X5R226K6R3FT"))
    )
    (comp (ref "L1")
      (value "2.2uH")
      (footprint "easyedapro:IND-SMD_L4.0-W4.0")
      (fields (field (name "Manufacturer Part") "SPH4018H2R2MT") (field (name "Manufacturer") "Sunlord(顺络)"))
      (libsource (lib "easyedapro") (part "SPH4018H2R2MT"))
    )
    (comp (ref "L2")
      (value "GZ1608D601TF")
      (footprint "easyedapro:L0603")
      (fields (field (name "Manufacturer") "Sunlord(顺络)"))
      (libsource (lib "easyedapro") (part "GZ1608D601TF"))
    )
    (comp (ref "R32")
      (value "5.1kΩ")
      (footprint "easyedapro:R0603")
      (fields
        (field (name "Manufacturer Part") "0603WAF5101T5E")
        (field (name "Manufacturer") "UNI-ROYAL(厚声)")
      )
      (libsource (lib "easyedapro") (part "0603WAF5101T5E"))
    )
    (comp (ref "R33")
      (value "5.1kΩ")
      (footprint "easyedapro:R0603")
      (fields
        (field (name "Manufacturer Part") "0603WAF5101T5E")
        (field (name "Manufacturer") "UNI-ROYAL(厚声)")
      )
      (libsource (lib "easyedapro") (part "0603WAF5101T5E"))
    )
    (comp (ref "R34")
      (value "22kΩ")
      (footprint "easyedapro:R0603")
      (fields
        (field (name "Manufacturer Part") "0603WAF2202T5E")
        (field (name "Manufacturer") "UNI-ROYAL(厚声)")
      )
      (libsource (lib "easyedapro") (part "0603WAF2372T5E"))
    )
    (comp (ref "R35")
      (value "68kΩ")
      (footprint "easyedapro:R0603")
      (fields
        (field (name "Manufacturer Part") "0603WAF6802T5E")
        (field (name "Manufacturer") "UNI-ROYAL(厚声)")
      )
      (libsource (lib "easyedapro") (part "RC0603FR-07453KL"))
    )
    (comp (ref "R36")
      (value "15kΩ")
      (footprint "easyedapro:R0603")
      (fields
        (field (name "Manufacturer Part") "0603WAF1502T5E")
        (field (name "Manufacturer") "UNI-ROYAL(厚声)")
      )
      (libsource (lib "easyedapro") (part "RC0603FR-07100KL"))
    )
    (comp (ref "U24")
      (value "TPS2553DBVR")
      (footprint "easyedapro:SOT-23-6_L2.9-W1.6-P0.95-LS2.8-BL")
      (fields (field (name "Manufacturer") "TI(德州仪器)"))
      (libsource (lib "easyedapro") (part "TPS2553DBVR-1"))
    )
    (comp (ref "U25")
      (value "SY8089AAAC")
      (footprint "easyedapro:SOT-23-5_L3.0-W1.7-P0.95-LS2.8-BR")
      (fields (field (name "Manufacturer") "Silergy(矽力杰)"))
      (libsource (lib "easyedapro") (part "SY8089AAAC"))
    )
    (comp (ref "U26")
      (value "AP2112K-3.3TRG1")
      (footprint "easyedapro:SOT-25-5_L2.9-W1.6-P0.95-LS2.8-BL")
      (fields (field (name "Manufacturer") "DIODES(美台)"))
      (libsource (lib "easyedapro") (part "AP2112K-3.3TRG1"))
    )
    (comp (ref "U27")
      (value "USBLC6-2SC6")
      (footprint "easyedapro:SOT-23-6_L2.9-W1.6-P0.95-LS2.8-BL")
      (fields (field (name "Manufacturer") "ST(意法半导体)"))
      (libsource (lib "easyedapro") (part "USBLC6-2SC6"))
    )
    (comp (ref "USBC1")
      (value "TYPE-C-31-M-12")
      (footprint "easyedapro:USB-C_SMD-TYPE-C-31-M-12_1")
      (fields (field (name "Manufacturer") "韩国韩荣"))
      (libsource (lib "easyedapro") (part "TYPE-C-31-M-12"))
    )
    (comp (ref "C1")
      (value "100nF")
      (footprint "easyedapro:C0603")
      (description "Capacitance:100nF Tolerance:±10% Tolerance:±10% Voltage Rating:50V Temperature Coefficient:X7R")
      (fields
        (field (name "Manufacturer Part") "CC0603KRX7R9BB104")
        (field (name "Manufacturer") "YAGEO(国巨)")
      )
      (libsource (lib "easyedapro") (part "CC0603KRX7R9BB104"))
    )
    (comp (ref "C2")
      (value "100nF")
      (footprint "easyedapro:C0603")
      (description "Capacitance:100nF Tolerance:±10% Tolerance:±10% Voltage Rating:50V Temperature Coefficient:X7R")
      (fields
        (field (name "Manufacturer Part") "CC0603KRX7R9BB104")
        (field (name "Manufacturer") "YAGEO(国巨)")
      )
      (libsource (lib "easyedapro") (part "CC0603KRX7R9BB104"))
    )
    (comp (ref "C3")
      (value "100nF")
      (footprint "easyedapro:C0603")
      (description "Capacitance:100nF Tolerance:±10% Tolerance:±10% Voltage Rating:50V Temperature Coefficient:X7R")
      (fields
        (field (name "Manufacturer Part") "CC0603KRX7R9BB104")
        (field (name "Manufacturer") "YAGEO(国巨)")
      )
      (libsource (lib "easyedapro") (part "CC0603KRX7R9BB104"))
    )
    (comp (ref "C6")
      (value "100nF")
      (footprint "easyedapro:C0603")
      (description "Capacitance:100nF Tolerance:±10% Tolerance:±10% Voltage Rating:50V Temperature Coefficient:X7R")
      (fields
        (field (name "Manufacturer Part") "CC0603KRX7R9BB104")
        (field (name "Manufacturer") "YAGEO(国巨)")
      )
      (libsource (lib "easyedapro") (part "CC0603KRX7R9BB104"))
    )
    (comp (ref "C7")
      (value "100nF")
      (footprint "easyedapro:C0603")
      (description "Capacitance:100nF Tolerance:±10% Tolerance:±10% Voltage Rating:50V Temperature Coefficient:X7R")
      (fields
        (field (name "Manufacturer Part") "CC0603KRX7R9BB104")
        (field (name "Manufacturer") "YAGEO(国巨)")
      )
      (libsource (lib "easyedapro") (part "CC0603KRX7R9BB104"))
    )
    (comp (ref "C8")
      (value "1uF")
      (footprint "easyedapro:C0603")
      (fields
        (field (name "Manufacturer Part") "CL10A105KB8NNNC")
        (field (name "Manufacturer") "SAMSUNG(三星)")
      )
      (libsource (lib "easyedapro") (part "0603B105K160"))
    )
    (comp (ref "C9")
      (value "22uF")
      (footprint "easyedapro:C0805")
      (description "Capacitance:22uF Tolerance:±10% Tolerance:±10% Voltage Rating:6.3V Temperature Coefficient:X5R")
      (fields
        (field (name "Manufacturer Part") "CL31A226KAHNNNE")
        (field (name "Manufacturer") "SAMSUNG(三星)")
      )
      (libsource (lib "easyedapro") (part "TCC0805X5R226K6R3FT"))
    )
    (comp (ref "C10")
      (value "4.7nF")
      (footprint "easyedapro:C0603")
      (description "Capacitance:4.7nF Tolerance:±10% Tolerance:±10% Voltage Rating:50V Temperature Coefficient:X7R")
      (fields (field (name "Manufacturer Part") "0603B472K500NT") (field (name "Manufacturer") "FH(风华)"))
      (libsource (lib "easyedapro") (part "CC0603KRX7R9BB472"))
    )
    (comp (ref "C11")
      (value "100nF")
      (footprint "easyedapro:C0603")
      (description "Capacitance:100nF Tolerance:±10% Tolerance:±10% Voltage Rating:50V Temperature Coefficient:X7R")
      (fields
        (field (name "Manufacturer Part") "CC0603KRX7R9BB104")
        (field (name "Manufacturer") "YAGEO(国巨)")
      )
      (libsource (lib "easyedapro") (part "CC0603KRX7R9BB104"))
    )
    (comp (ref "R1")
      (value "1kΩ")
      (footprint "easyedapro:R0603")
      (fields
        (field (name "Manufacturer Part") "0603WAF1001T5E")
        (field (name "Manufacturer") "UNI-ROYAL(厚声)")
      )
      (libsource (lib "easyedapro") (part "RC0603FR-071KL"))
    )
    (comp (ref "R2")
      (value "500mΩ")
      (footprint "easyedapro:R1206")
      (fields
        (field (name "Manufacturer Part") "HoYH1206-1W-500mR-1%")
        (field (name "Manufacturer") "Milliohm(毫欧)")
      )
      (libsource (lib "easyedapro") (part "HOYH1206-1W-500MR-1%"))
    )
    (comp (ref "R3")
      (value "10kΩ")
      (footprint "easyedapro:R0603")
      (fields
        (field (name "Manufacturer Part") "0603WAF1002T5E")
        (field (name "Manufacturer") "UNI-ROYAL(厚声)")
      )
      (libsource (lib "easyedapro") (part "RC0603FR-0710KL"))
    )
    (comp (ref "R6")
      (value "12kΩ")
      (footprint "easyedapro:R0603")
      (fields
        (field (name "Manufacturer Part") "0603WAF1202T5E")
        (field (name "Manufacturer") "UNI-ROYAL(厚声)")
      )
      (libsource (lib "easyedapro") (part "RC0603FR-0710KL"))
    )
    (comp (ref "R7")
      (value "10kΩ")
      (footprint "easyedapro:R0603")
      (fields
        (field (name "Manufacturer Part") "0603WAF1002T5E")
        (field (name "Manufacturer") "UNI-ROYAL(厚声)")
      )
      (libsource (lib "easyedapro") (part "RC0603FR-0710KL"))
    )
    (comp (ref "R8")
      (value "1kΩ")
      (footprint "easyedapro:R0603")
      (fields
        (field (name "Manufacturer Part") "0603WAF1001T5E")
        (field (name "Manufacturer") "UNI-ROYAL(厚声)")
      )
      (libsource (lib "easyedapro") (part "RC0603FR-071KL"))
    )
    (comp (ref "R9")
      (value "100kΩ")
      (footprint "easyedapro:R0603")
      (fields
        (field (name "Manufacturer Part") "0603WAF1003T5E")
        (field (name "Manufacturer") "UNI-ROYAL(厚声)")
      )
      (libsource (lib "easyedapro") (part "RC0603FR-07100KL"))
    )
    (comp (ref "R10")
      (value "100kΩ")
      (footprint "easyedapro:R0603")
      (fields
        (field (name "Manufacturer Part") "0603WAF1003T5E")
        (field (name "Manufacturer") "UNI-ROYAL(厚声)")
      )
      (libsource (lib "easyedapro") (part "RC0603FR-07100KL"))
    )
    (comp (ref "R11")
      (value "10kΩ")
      (footprint "easyedapro:R0603")
      (fields
        (field (name "Manufacturer Part") "0603WAF1002T5E")
        (field (name "Manufacturer") "UNI-ROYAL(厚声)")
      )
      (libsource (lib "easyedapro") (part "RC0603FR-0710KL"))
    )
    (comp (ref "R12")
      (value "4.7kΩ")
      (footprint "easyedapro:R0603")
      (fields
        (field (name "Manufacturer Part") "0603WAF4701T5E")
        (field (name "Manufacturer") "UNI-ROYAL(厚声)")
      )
      (libsource (lib "easyedapro") (part "RC0603FR-074K7L"))
    )
    (comp (ref "R13")
      (value "1kΩ")
      (footprint "easyedapro:R0603")
      (fields
        (field (name "Manufacturer Part") "0603WAF1001T5E")
        (field (name "Manufacturer") "UNI-ROYAL(厚声)")
      )
      (libsource (lib "easyedapro") (part "RC0603FR-071KL"))
    )
    (comp (ref "R14")
      (value "4.7kΩ")
      (footprint "easyedapro:R0603")
      (fields
        (field (name "Manufacturer Part") "0603WAF4701T5E")
        (field (name "Manufacturer") "UNI-ROYAL(厚声)")
      )
      (libsource (lib "easyedapro") (part "RC0603FR-074K7L"))
    )
    (comp (ref "R15")
      (value "100kΩ")
      (footprint "easyedapro:R0603")
      (fields
        (field (name "Manufacturer Part") "0603WAF1003T5E")
        (field (name "Manufacturer") "UNI-ROYAL(厚声)")
      )
      (libsource (lib "easyedapro") (part "RC0603FR-07100KL"))
    )
    (comp (ref "R16")
      (value "10kΩ")
      (footprint "easyedapro:R0603")
      (fields
        (field (name "Manufacturer Part") "0603WAF1002T5E")
        (field (name "Manufacturer") "UNI-ROYAL(厚声)")
      )
      (libsource (lib "easyedapro") (part "RC0603FR-0710KL"))
    )
    (comp (ref "TP1")
      (value "CURRENT_RAW")
      (footprint "easyedapro:Test-Point-0.5mm")
      (description "Test Point 测试点")
      (fields (field (name "Add into BOM") "no"))
      (libsource (lib "easyedapro") (part "Test-Point"))
    )
    (comp (ref "TP2")
      (value "ADC_CURRENT")
      (footprint "easyedapro:Test-Point-0.5mm")
      (description "Test Point 测试点")
      (fields (field (name "Add into BOM") "no"))
      (libsource (lib "easyedapro") (part "Test-Point"))
    )
    (comp (ref "TP4")
      (value "TACHO_AMP")
      (footprint "easyedapro:Test-Point-0.5mm")
      (description "Test Point 测试点")
      (fields (field (name "Add into BOM") "no"))
      (libsource (lib "easyedapro") (part "Test-Point"))
    )
    (comp (ref "TP5")
      (value "~")
      (footprint "easyedapro:Test-Point-0.5mm")
      (description "Test Point 测试点")
      (fields (field (name "Add into BOM") "no"))
      (libsource (lib "easyedapro") (part "Test-Point"))
    )
    (comp (ref "U1")
      (value "INA180A1IDBVR")
      (footprint "easyedapro:SOT-23-5_L3.0-W1.7-P0.95-LS2.8-BR")
      (fields (field (name "Manufacturer") "TI(德州仪器)"))
      (libsource (lib "easyedapro") (part "INA180A1IDBVR"))
    )
    (comp (ref "U3")
      (value "LMV393IDR")
      (footprint "easyedapro:SOIC-8_L5.0-W4.0-P1.27-LS6.0-BL")
      (fields (field (name "Manufacturer") "TI(德州仪器)"))
      (libsource (lib "easyedapro") (part "LMV393IDR"))
    )
    (comp (ref "U5")
      (value "TLV9001IDBVR")
      (footprint "easyedapro:SOT-23-5_L3.0-W1.7-P0.95-LS2.8-BR")
      (fields (field (name "Manufacturer") "TI(德州仪器)"))
      (libsource (lib "easyedapro") (part "TLV9001IDBVR"))
    )
  )
  (nets
    (net (code "1") (name "3V3_ANALOG") (class "Default")
      (node (ref "C2") (pin "1") (pinfunction "1_1") (pintype "unspecified"))
      (node (ref "C35") (pin "1") (pinfunction "1_1") (pintype "unspecified"))
      (node (ref "C36") (pin "2") (pinfunction "2_2") (pintype "unspecified"))
      (node (ref "C7") (pin "2") (pinfunction "2_2") (pintype "unspecified"))
      (node (ref "L2") (pin "1") (pinfunction "1_1") (pintype "unspecified"))
      (node (ref "R11") (pin "2") (pinfunction "2_2") (pintype "input"))
      (node (ref "R6") (pin "2") (pinfunction "2_2") (pintype "input"))
      (node (ref "TP-3v3Analog") (pin "1") (pinfunction "1_1") (pintype "unspecified"))
      (node (ref "U1") (pin "5") (pinfunction "VS_5") (pintype "unspecified"))
      (node (ref "U5") (pin "5") (pinfunction "V+_5") (pintype "unspecified"))
    )
    (net (code "2") (name "3V3_EXT") (class "Default")
      (node (ref "J1") (pin "1") (pinfunction "1_1") (pintype "unspecified"))
      (node (ref "R43") (pin "2") (pinfunction "2_2") (pintype "input"))
      (node (ref "U29") (pin "2") (pinfunction "2_2") (pintype "unspecified"))
    )
    (net (code "3") (name "3V3_EXT_FUSED") (class "Default")
      (node (ref "F1") (pin "2") (pinfunction "2_2") (pintype "unspecified"))
      (node (ref "R43") (pin "1") (pinfunction "1_1") (pintype "input"))
    )
    (net (code "4") (name "3V3_LOGIC") (class "Default")
      (node (ref "C14") (pin "2") (pinfunction "2_2") (pintype "unspecified"))
      (node (ref "C15") (pin "2") (pinfunction "2_2") (pintype "unspecified"))
      (node (ref "C17") (pin "1") (pinfunction "1_1") (pintype "unspecified"))
      (node (ref "C18") (pin "2") (pinfunction "2_2") (pintype "unspecified"))
      (node (ref "C37") (pin "2") (pinfunction "2_2") (pintype "unspecified"))
      (node (ref "C38") (pin "2") (pinfunction "2_2") (pintype "unspecified"))
      (node (ref "F1") (pin "1") (pinfunction "1_1") (pintype "unspecified"))
      (node (ref "J8") (pin "2") (pinfunction "2_2") (pintype "unspecified"))
      (node (ref "J9") (pin "2") (pinfunction "2_2") (pintype "unspecified"))
      (node (ref "L1") (pin "1") (pinfunction "1_1") (pintype "input"))
      (node (ref "L2") (pin "2") (pinfunction "2_2") (pintype "unspecified"))
      (node (ref "R16") (pin "1") (pinfunction "1_1") (pintype "input"))
      (node (ref "R21") (pin "2") (pinfunction "2_2") (pintype "input"))
      (node (ref "R23") (pin "2") (pinfunction "2_2") (pintype "input"))
      (node (ref "R24") (pin "2") (pinfunction "2_2") (pintype "input"))
      (node (ref "R25") (pin "2") (pinfunction "2_2") (pintype "input"))
      (node (ref "R3") (pin "2") (pinfunction "2_2") (pintype "input"))
      (node (ref "R35") (pin "1") (pinfunction "1_1") (pintype "unspecified"))
      (node (ref "R37") (pin "1") (pinfunction "1_1") (pintype "input"))
      (node (ref "R38") (pin "2") (pinfunction "2_2") (pintype "input"))
      (node (ref "R41") (pin "2") (pinfunction "2_2") (pintype "input"))
      (node (ref "R42") (pin "1") (pinfunction "1_1") (pintype "input"))
      (node (ref "TP-3v3Logic") (pin "1") (pinfunction "1_1") (pintype "unspecified"))
      (node (ref "U28") (pin "24") (pinfunction "VCC_24") (pintype "input"))
      (node (ref "U6") (pin "2") (pinfunction "3V3_2") (pintype "unspecified"))
      (node (ref "U7") (pin "5") (pinfunction "VCC_5") (pintype "input"))
    )
    (net (code "5") (name "3V3_MOTOR") (class "Default")
      (node (ref "C21") (pin "2") (pinfunction "2_2") (pintype "unspecified"))
      (node (ref "C22") (pin "2") (pinfunction "2_2") (pintype "unspecified"))
      (node (ref "C25") (pin "2") (pinfunction "2_2") (pintype "unspecified"))
      (node (ref "C26") (pin "2") (pinfunction "2_2") (pintype "unspecified"))
      (node (ref "C29") (pin "2") (pinfunction "2_2") (pintype "unspecified"))
      (node (ref "C30") (pin "2") (pinfunction "2_2") (pintype "unspecified"))
      (node (ref "R2") (pin "2") (pinfunction "2_2") (pintype "unspecified"))
      (node (ref "TP-3v3Motor") (pin "1") (pinfunction "1_1") (pintype "unspecified"))
      (node (ref "U1") (pin "4") (pinfunction "IN-_4") (pintype "unspecified"))
      (node (ref "U10") (pin "12") (pinfunction "VM_12") (pintype "unspecified"))
      (node (ref "U11") (pin "12") (pinfunction "VM_12") (pintype "unspecified"))
      (node (ref "U9") (pin "12") (pinfunction "VM_12") (pintype "unspecified"))
    )
    (net (code "6") (name "3V3_MOTOR_REG") (class "Default")
      (node (ref "C39") (pin "2") (pinfunction "2_2") (pintype "unspecified"))
      (node (ref "C40") (pin "2") (pinfunction "2_2") (pintype "unspecified"))
      (node (ref "C41") (pin "2") (pinfunction "2_2") (pintype "unspecified"))
      (node (ref "R2") (pin "1") (pinfunction "1_1") (pintype "unspecified"))
      (node (ref "U1") (pin "3") (pinfunction "IN+_3") (pintype "unspecified"))
      (node (ref "U26") (pin "5") (pinfunction "VOUT_5") (pintype "unspecified"))
    )
    (net (code "7") (name "ADC_CURRENT") (class "Default")
      (node (ref "C1") (pin "2") (pinfunction "2_2") (pintype "unspecified"))
      (node (ref "R1") (pin "1") (pinfunction "1_1") (pintype "input"))
      (node (ref "TP2") (pin "1") (pinfunction "1_1") (pintype "unspecified"))
      (node (ref "U6") (pin "38") (pinfunction "IO2_38") (pintype "unspecified"))
    )
    (net (code "8") (name "ADC_TACHO") (class "Default")
      (node (ref "R13") (pin "2") (pinfunction "2_2") (pintype "input"))
      (node (ref "U6") (pin "39") (pinfunction "IO1_39") (pintype "unspecified"))
    )
    (net (code "9") (name "AISEN1") (class "Default")
      (node (ref "RSA1") (pin "2") (pinfunction "2_2") (pintype "input"))
      (node (ref "U9") (pin "3") (pinfunction "AISEN_3") (pintype "unspecified"))
    )
    (net (code "10") (name "AISEN3") (class "Default")
      (node (ref "RSA2") (pin "2") (pinfunction "2_2") (pintype "input"))
      (node (ref "U10") (pin "3") (pinfunction "AISEN_3") (pintype "unspecified"))
    )
    (net (code "11") (name "AISEN5") (class "Default")
      (node (ref "RSA3") (pin "2") (pinfunction "2_2") (pintype "input"))
      (node (ref "U11") (pin "3") (pinfunction "AISEN_3") (pintype "unspecified"))
    )
    (net (code "12") (name "BISEN2") (class "Default")
      (node (ref "RSB1") (pin "2") (pinfunction "2_2") (pintype "input"))
      (node (ref "U9") (pin "6") (pinfunction "BISEN_6") (pintype "unspecified"))
    )
    (net (code "13") (name "BISEN4") (class "Default")
      (node (ref "RSB2") (pin "2") (pinfunction "2_2") (pintype "input"))
      (node (ref "U10") (pin "6") (pinfunction "BISEN_6") (pintype "unspecified"))
    )
    (net (code "14") (name "BISEN6") (class "Default")
      (node (ref "RSB3") (pin "2") (pinfunction "2_2") (pintype "input"))
      (node (ref "U11") (pin "6") (pinfunction "BISEN_6") (pintype "unspecified"))
    )
    (net (code "15") (name "BOOT_N") (class "Default")
      (node (ref "BOOT") (pin "1") (pinfunction "1_1") (pintype "unspecified"))
      (node (ref "R25") (pin "1") (pinfunction "1_1") (pintype "input"))
      (node (ref "U6") (pin "27") (pinfunction "IO0_27") (pintype "unspecified"))
    )
    (net (code "16") (name "COMM_TACHO_N") (class "Default")
      (node (ref "R15") (pin "2") (pinfunction "2_2") (pintype "input"))
      (node (ref "R16") (pin "2") (pinfunction "2_2") (pintype "input"))
      (node (ref "TP5") (pin "1") (pinfunction "1_1") (pintype "unspecified"))
      (node (ref "U3") (pin "7") (pinfunction "2OUT_7") (pintype "unspecified"))
      (node (ref "U6") (pin "31") (pinfunction "IO38_31") (pintype "unspecified"))
    )
    (net (code "17") (name "CURRENT_RAW") (class "Default")
      (node (ref "C8") (pin "2") (pinfunction "2_2") (pintype "input"))
      (node (ref "R1") (pin "2") (pinfunction "2_2") (pintype "input"))
      (node (ref "TP1") (pin "1") (pinfunction "1_1") (pintype "unspecified"))
      (node (ref "U1") (pin "1") (pinfunction "OUT_1") (pintype "unspecified"))
      (node (ref "U3") (pin "2") (pinfunction "1IN-_2") (pintype "unspecified"))
    )
    (net (code "18") (name "DECODER_INHIBIT") (class "Default")
      (node (ref "TP-Decoder-Inhibit") (pin "1") (pinfunction "1_1") (pintype "unspecified"))
      (node (ref "U28") (pin "1") (pinfunction "LE_1") (pintype "input"))
      (node (ref "U28") (pin "23") (pinfunction "E_23") (pintype "input"))
      (node (ref "U7") (pin "4") (pinfunction "Y_4") (pintype "input"))
    )
    (net (code "19") (name "DRIVER_N_SLEEP") (class "Default")
      (node (ref "R31") (pin "1") (pinfunction "1_1") (pintype "input"))
      (node (ref "U10") (pin "1") (pinfunction "nSLEEP_1") (pintype "unspecified"))
      (node (ref "U11") (pin "1") (pinfunction "nSLEEP_1") (pintype "unspecified"))
      (node (ref "U6") (pin "10") (pinfunction "IO17_10") (pintype "unspecified"))
      (node (ref "U7") (pin "2") (pinfunction "B_2") (pintype "input"))
      (node (ref "U9") (pin "1") (pinfunction "nSLEEP_1") (pintype "unspecified"))
    )
    (net (code "20") (name "ESP_EN") (class "Default")
      (node (ref "C16") (pin "2") (pinfunction "2_2") (pintype "input"))
      (node (ref "R24") (pin "1") (pinfunction "1_1") (pintype "input"))
      (node (ref "RESET") (pin "2") (pinfunction "2_2") (pintype "unspecified"))
      (node (ref "U6") (pin "3") (pinfunction "EN_3") (pintype "unspecified"))
    )
    (net (code "21") (name "FAULT_N_RAW") (class "Default")
      (node (ref "C3") (pin "1") (pinfunction "1_1") (pintype "unspecified"))
      (node (ref "R3") (pin "1") (pinfunction "1_1") (pintype "input"))
      (node (ref "U10") (pin "8") (pinfunction "nFAULT_8") (pintype "unspecified"))
      (node (ref "U11") (pin "8") (pinfunction "nFAULT_8") (pintype "unspecified"))
      (node (ref "U6") (pin "9") (pinfunction "IO16_9") (pintype "unspecified"))
      (node (ref "U9") (pin "8") (pinfunction "nFAULT_8") (pintype "unspecified"))
    )
    (net (code "22") (name "FAULT_USB_RAW") (class "Default")
      (node (ref "C42") (pin "2") (pinfunction "2_2") (pintype "input"))
      (node (ref "R42") (pin "2") (pinfunction "2_2") (pintype "input"))
      (node (ref "U24") (pin "4") (pinfunction "FAULT#_4") (pintype "input"))
      (node (ref "U6") (pin "8") (pinfunction "IO15_8") (pintype "unspecified"))
    )
    (net (code "23") (name "FLIM_REF") (class "Default")
      (node (ref "C6") (pin "2") (pinfunction "2_2") (pintype "unspecified"))
      (node (ref "R6") (pin "1") (pinfunction "1_1") (pintype "input"))
      (node (ref "R7") (pin "2") (pinfunction "2_2") (pintype "input"))
      (node (ref "U3") (pin "3") (pinfunction "1IN+_3") (pintype "unspecified"))
    )
    (net (code "24") (name "FWD1") (class "Default")
      (node (ref "U28") (pin "4") (pinfunction "Q7_4") (pintype "input"))
      (node (ref "U9") (pin "16") (pinfunction "AIN1_16") (pintype "unspecified"))
    )
    (net (code "25") (name "FWD2") (class "Default")
      (node (ref "U28") (pin "7") (pinfunction "Q4_7") (pintype "input"))
      (node (ref "U9") (pin "9") (pinfunction "BIN1_9") (pintype "unspecified"))
    )
    (net (code "26") (name "FWD3") (class "Default")
      (node (ref "U10") (pin "16") (pinfunction "AIN1_16") (pintype "unspecified"))
      (node (ref "U28") (pin "13") (pinfunction "Q13_13") (pintype "input"))
    )
    (net (code "27") (name "FWD4") (class "Default")
      (node (ref "U10") (pin "9") (pinfunction "BIN1_9") (pintype "unspecified"))
      (node (ref "U28") (pin "16") (pinfunction "Q14_16") (pintype "input"))
    )
    (net (code "28") (name "FWD5") (class "Default")
      (node (ref "U11") (pin "16") (pinfunction "AIN1_16") (pintype "unspecified"))
      (node (ref "U28") (pin "17") (pinfunction "Q9_17") (pintype "input"))
    )
    (net (code "29") (name "FWD6") (class "Default")
      (node (ref "U11") (pin "9") (pinfunction "BIN1_9") (pintype "unspecified"))
      (node (ref "U28") (pin "20") (pinfunction "Q10_20") (pintype "input"))
    )
    (net (code "30") (name "GND") (class "Default")
      (node (ref "BOOT") (pin "2") (pinfunction "2_2") (pintype "unspecified"))
      (node (ref "C1") (pin "1") (pinfunction "1_1") (pintype "unspecified"))
      (node (ref "C11") (pin "2") (pinfunction "2_2") (pintype "unspecified"))
      (node (ref "C14") (pin "1") (pinfunction "1_1") (pintype "unspecified"))
      (node (ref "C15") (pin "1") (pinfunction "1_1") (pintype "unspecified"))
      (node (ref "C16") (pin "1") (pinfunction "1_1") (pintype "input"))
      (node (ref "C17") (pin "2") (pinfunction "2_2") (pintype "unspecified"))
      (node (ref "C18") (pin "1") (pinfunction "1_1") (pintype "unspecified"))
      (node (ref "C2") (pin "2") (pinfunction "2_2") (pintype "unspecified"))
      (node (ref "C21") (pin "1") (pinfunction "1_1") (pintype "unspecified"))
      (node (ref "C22") (pin "1") (pinfunction "1_1") (pintype "unspecified"))
      (node (ref "C25") (pin "1") (pinfunction "1_1") (pintype "unspecified"))
      (node (ref "C26") (pin "1") (pinfunction "1_1") (pintype "unspecified"))
      (node (ref "C29") (pin "1") (pinfunction "1_1") (pintype "unspecified"))
      (node (ref "C3") (pin "2") (pinfunction "2_2") (pintype "unspecified"))
      (node (ref "C30") (pin "1") (pinfunction "1_1") (pintype "unspecified"))
      (node (ref "C31") (pin "1") (pinfunction "1_1") (pintype "input"))
      (node (ref "C32") (pin "1") (pinfunction "1_1") (pintype "unspecified"))
      (node (ref "C33") (pin "1") (pinfunction "1_1") (pintype "unspecified"))
      (node (ref "C34") (pin "1") (pinfunction "1_1") (pintype "unspecified"))
      (node (ref "C35") (pin "2") (pinfunction "2_2") (pintype "unspecified"))
      (node (ref "C36") (pin "1") (pinfunction "1_1") (pintype "unspecified"))
      (node (ref "C37") (pin "1") (pinfunction "1_1") (pintype "unspecified"))
      (node (ref "C38") (pin "1") (pinfunction "1_1") (pintype "unspecified"))
      (node (ref "C39") (pin "1") (pinfunction "1_1") (pintype "unspecified"))
      (node (ref "C40") (pin "1") (pinfunction "1_1") (pintype "unspecified"))
      (node (ref "C41") (pin "1") (pinfunction "1_1") (pintype "unspecified"))
      (node (ref "C42") (pin "1") (pinfunction "1_1") (pintype "input"))
      (node (ref "C43") (pin "2") (pinfunction "2_2") (pintype "input"))
      (node (ref "C6") (pin "1") (pinfunction "1_1") (pintype "unspecified"))
      (node (ref "C7") (pin "1") (pinfunction "1_1") (pintype "unspecified"))
      (node (ref "C9") (pin "1") (pinfunction "1_1") (pintype "unspecified"))
      (node (ref "J1") (pin "3") (pinfunction "3_3") (pintype "unspecified"))
      (node (ref "J8") (pin "1") (pinfunction "1_1") (pintype "unspecified"))
      (node (ref "J9") (pin "1") (pinfunction "1_1") (pintype "unspecified"))
      (node (ref "R12") (pin "1") (pinfunction "1_1") (pintype "input"))
      (node (ref "R26") (pin "1") (pinfunction "1_1") (pintype "input"))
      (node (ref "R27") (pin "1") (pinfunction "1_1") (pintype "input"))
      (node (ref "R28") (pin "1") (pinfunction "1_1") (pintype "input"))
      (node (ref "R29") (pin "1") (pinfunction "1_1") (pintype "input"))
      (node (ref "R30") (pin "1") (pinfunction "1_1") (pintype "input"))
      (node (ref "R31") (pin "2") (pinfunction "2_2") (pintype "input"))
      (node (ref "R32") (pin "2") (pinfunction "2_2") (pintype "input"))
      (node (ref "R33") (pin "2") (pinfunction "2_2") (pintype "input"))
      (node (ref "R34") (pin "2") (pinfunction "2_2") (pintype "input"))
      (node (ref "R36") (pin "2") (pinfunction "2_2") (pintype "input"))
      (node (ref "R7") (pin "1") (pinfunction "1_1") (pintype "input"))
      (node (ref "RESET") (pin "1") (pinfunction "1_1") (pintype "unspecified"))
      (node (ref "RSA1") (pin "1") (pinfunction "1_1") (pintype "input"))
      (node (ref "RSA2") (pin "1") (pinfunction "1_1") (pintype "input"))
      (node (ref "RSA3") (pin "1") (pinfunction "1_1") (pintype "input"))
      (node (ref "RSB1") (pin "1") (pinfunction "1_1") (pintype "input"))
      (node (ref "RSB2") (pin "1") (pinfunction "1_1") (pintype "input"))
      (node (ref "RSB3") (pin "1") (pinfunction "1_1") (pintype "input"))
      (node (ref "U1") (pin "2") (pinfunction "GND_2") (pintype "unspecified"))
      (node (ref "U10") (pin "13") (pinfunction "GND_13") (pintype "unspecified"))
      (node (ref "U10") (pin "17") (pinfunction "EP_17") (pintype "unspecified"))
      (node (ref "U11") (pin "13") (pinfunction "GND_13") (pintype "unspecified"))
      (node (ref "U11") (pin "17") (pinfunction "EP_17") (pintype "unspecified"))
      (node (ref "U12") (pin "2") (pinfunction "2_2") (pintype "unspecified"))
      (node (ref "U13") (pin "2") (pinfunction "2_2") (pintype "unspecified"))
      (node (ref "U14") (pin "2") (pinfunction "2_2") (pintype "unspecified"))
      (node (ref "U15") (pin "2") (pinfunction "2_2") (pintype "unspecified"))
      (node (ref "U16") (pin "2") (pinfunction "2_2") (pintype "unspecified"))
      (node (ref "U17") (pin "2") (pinfunction "2_2") (pintype "unspecified"))
      (node (ref "U18") (pin "2") (pinfunction "2_2") (pintype "unspecified"))
      (node (ref "U19") (pin "2") (pinfunction "2_2") (pintype "unspecified"))
      (node (ref "U20") (pin "2") (pinfunction "2_2") (pintype "unspecified"))
      (node (ref "U21") (pin "2") (pinfunction "2_2") (pintype "unspecified"))
      (node (ref "U22") (pin "2") (pinfunction "2_2") (pintype "unspecified"))
      (node (ref "U23") (pin "2") (pinfunction "2_2") (pintype "unspecified"))
      (node (ref "U24") (pin "2") (pinfunction "GND_2") (pintype "input"))
      (node (ref "U25") (pin "2") (pinfunction "GND_2") (pintype "unspecified"))
      (node (ref "U26") (pin "2") (pinfunction "GND_2") (pintype "unspecified"))
      (node (ref "U27") (pin "2") (pinfunction "2_2") (pintype "input"))
      (node (ref "U28") (pin "12") (pinfunction "GND_12") (pintype "input"))
      (node (ref "U29") (pin "1") (pinfunction "1_1") (pintype "unspecified"))
      (node (ref "U3") (pin "4") (pinfunction "GND_4") (pintype "unspecified"))
      (node (ref "U30") (pin "1") (pinfunction "1_1") (pintype "unspecified"))
      (node (ref "U5") (pin "2") (pinfunction "V-_2") (pintype "unspecified"))
      (node (ref "U6") (pin "1") (pinfunction "GND_1") (pintype "unspecified"))
      (node (ref "U6") (pin "40") (pinfunction "GND_40") (pintype "unspecified"))
      (node (ref "U6") (pin "41") (pinfunction "GND_41") (pintype "unspecified"))
      (node (ref "U7") (pin "3") (pinfunction "GND_3") (pintype "input"))
      (node (ref "U9") (pin "13") (pinfunction "GND_13") (pintype "unspecified"))
      (node (ref "U9") (pin "17") (pinfunction "EP_17") (pintype "unspecified"))
      (node (ref "USBC1") (pin "1") (pinfunction "EH_1") (pintype "unspecified"))
      (node (ref "USBC1") (pin "2") (pinfunction "EH_2") (pintype "unspecified"))
      (node (ref "USBC1") (pin "3") (pinfunction "EH_3") (pintype "unspecified"))
      (node (ref "USBC1") (pin "4") (pinfunction "EH_4") (pintype "unspecified"))
      (node (ref "USBC1") (pin "A1B12") (pinfunction "GND_A1B12") (pintype "unspecified"))
      (node (ref "USBC1") (pin "B1A12") (pinfunction "GND_B1A12") (pintype "unspecified"))
    )
    (net (code "31") (name "I2C_SCL") (class "Default")
      (node (ref "J8") (pin "3") (pinfunction "3_3") (pintype "unspecified"))
      (node (ref "R37") (pin "2") (pinfunction "2_2") (pintype "input"))
      (node (ref "U6") (pin "24") (pinfunction "IO47_24") (pintype "unspecified"))
    )
    (net (code "32") (name "I2C_SDA") (class "Default")
      (node (ref "J8") (pin "4") (pinfunction "4_4") (pintype "unspecified"))
      (node (ref "R38") (pin "1") (pinfunction "1_1") (pintype "input"))
      (node (ref "U6") (pin "23") (pinfunction "IO21_23") (pintype "unspecified"))
    )
    (net (code "33") (name "LOGIC_FB") (class "Default")
      (node (ref "R35") (pin "2") (pinfunction "2_2") (pintype "unspecified"))
      (node (ref "R36") (pin "1") (pinfunction "1_1") (pintype "input"))
      (node (ref "U25") (pin "5") (pinfunction "FB_5") (pintype "unspecified"))
    )
    (net (code "34") (name "LOGIC_SW") (class "Default")
      (node (ref "L1") (pin "2") (pinfunction "2_2") (pintype "input"))
      (node (ref "U25") (pin "3") (pinfunction "LX_3") (pintype "unspecified"))
    )
    (net (code "35") (name "MOTOR_1A") (class "Default")
      (node (ref "L3") (pin "1") (pinfunction "1_1") (pintype "unspecified"))
      (node (ref "U9") (pin "2") (pinfunction "AOUT1_2") (pintype "unspecified"))
    )
    (net (code "36") (name "MOTOR_1A_J") (class "Default")
      (node (ref "J2") (pin "1") (pinfunction "1_1") (pintype "unspecified"))
      (node (ref "L3") (pin "2") (pinfunction "2_2") (pintype "unspecified"))
      (node (ref "U12") (pin "1") (pinfunction "1_1") (pintype "unspecified"))
    )
    (net (code "37") (name "MOTOR_1B") (class "Default")
      (node (ref "L4") (pin "1") (pinfunction "1_1") (pintype "unspecified"))
      (node (ref "U9") (pin "4") (pinfunction "AOUT2_4") (pintype "unspecified"))
    )
    (net (code "38") (name "MOTOR_1B_J") (class "Default")
      (node (ref "J2") (pin "3") (pinfunction "3_3") (pintype "unspecified"))
      (node (ref "L4") (pin "2") (pinfunction "2_2") (pintype "unspecified"))
      (node (ref "U13") (pin "1") (pinfunction "1_1") (pintype "unspecified"))
    )
    (net (code "39") (name "MOTOR_2A") (class "Default")
      (node (ref "L5") (pin "1") (pinfunction "1_1") (pintype "unspecified"))
      (node (ref "U9") (pin "7") (pinfunction "BOUT1_7") (pintype "unspecified"))
    )
    (net (code "40") (name "MOTOR_2A_J") (class "Default")
      (node (ref "J3") (pin "1") (pinfunction "1_1") (pintype "unspecified"))
      (node (ref "L5") (pin "2") (pinfunction "2_2") (pintype "unspecified"))
      (node (ref "U14") (pin "1") (pinfunction "1_1") (pintype "unspecified"))
    )
    (net (code "41") (name "MOTOR_2B") (class "Default")
      (node (ref "L6") (pin "1") (pinfunction "1_1") (pintype "unspecified"))
      (node (ref "U9") (pin "5") (pinfunction "BOUT2_5") (pintype "unspecified"))
    )
    (net (code "42") (name "MOTOR_2B_J") (class "Default")
      (node (ref "J3") (pin "3") (pinfunction "3_3") (pintype "unspecified"))
      (node (ref "L6") (pin "2") (pinfunction "2_2") (pintype "unspecified"))
      (node (ref "U15") (pin "1") (pinfunction "1_1") (pintype "unspecified"))
    )
    (net (code "43") (name "MOTOR_3A") (class "Default")
      (node (ref "L7") (pin "1") (pinfunction "1_1") (pintype "unspecified"))
      (node (ref "U10") (pin "2") (pinfunction "AOUT1_2") (pintype "unspecified"))
    )
    (net (code "44") (name "MOTOR_3A_J") (class "Default")
      (node (ref "J4") (pin "1") (pinfunction "1_1") (pintype "unspecified"))
      (node (ref "L7") (pin "2") (pinfunction "2_2") (pintype "unspecified"))
      (node (ref "U16") (pin "1") (pinfunction "1_1") (pintype "unspecified"))
    )
    (net (code "45") (name "MOTOR_3B") (class "Default")
      (node (ref "L8") (pin "1") (pinfunction "1_1") (pintype "unspecified"))
      (node (ref "U10") (pin "4") (pinfunction "AOUT2_4") (pintype "unspecified"))
    )
    (net (code "46") (name "MOTOR_3B_J") (class "Default")
      (node (ref "J4") (pin "3") (pinfunction "3_3") (pintype "unspecified"))
      (node (ref "L8") (pin "2") (pinfunction "2_2") (pintype "unspecified"))
      (node (ref "U17") (pin "1") (pinfunction "1_1") (pintype "unspecified"))
    )
    (net (code "47") (name "MOTOR_4A") (class "Default")
      (node (ref "L9") (pin "1") (pinfunction "1_1") (pintype "unspecified"))
      (node (ref "U10") (pin "7") (pinfunction "BOUT1_7") (pintype "unspecified"))
    )
    (net (code "48") (name "MOTOR_4A_J") (class "Default")
      (node (ref "J5") (pin "1") (pinfunction "1_1") (pintype "unspecified"))
      (node (ref "L9") (pin "2") (pinfunction "2_2") (pintype "unspecified"))
      (node (ref "U18") (pin "1") (pinfunction "1_1") (pintype "unspecified"))
    )
    (net (code "49") (name "MOTOR_4B") (class "Default")
      (node (ref "L10") (pin "1") (pinfunction "1_1") (pintype "unspecified"))
      (node (ref "U10") (pin "5") (pinfunction "BOUT2_5") (pintype "unspecified"))
    )
    (net (code "50") (name "MOTOR_4B_J") (class "Default")
      (node (ref "J5") (pin "3") (pinfunction "3_3") (pintype "unspecified"))
      (node (ref "L10") (pin "2") (pinfunction "2_2") (pintype "unspecified"))
      (node (ref "U19") (pin "1") (pinfunction "1_1") (pintype "unspecified"))
    )
    (net (code "51") (name "MOTOR_5A") (class "Default")
      (node (ref "L11") (pin "1") (pinfunction "1_1") (pintype "unspecified"))
      (node (ref "U11") (pin "2") (pinfunction "AOUT1_2") (pintype "unspecified"))
    )
    (net (code "52") (name "MOTOR_5A_J") (class "Default")
      (node (ref "J6") (pin "1") (pinfunction "1_1") (pintype "unspecified"))
      (node (ref "L11") (pin "2") (pinfunction "2_2") (pintype "unspecified"))
      (node (ref "U20") (pin "1") (pinfunction "1_1") (pintype "unspecified"))
    )
    (net (code "53") (name "MOTOR_5B") (class "Default")
      (node (ref "L12") (pin "1") (pinfunction "1_1") (pintype "unspecified"))
      (node (ref "U11") (pin "4") (pinfunction "AOUT2_4") (pintype "unspecified"))
    )
    (net (code "54") (name "MOTOR_5B_J") (class "Default")
      (node (ref "J6") (pin "3") (pinfunction "3_3") (pintype "unspecified"))
      (node (ref "L12") (pin "2") (pinfunction "2_2") (pintype "unspecified"))
      (node (ref "U21") (pin "1") (pinfunction "1_1") (pintype "unspecified"))
    )
    (net (code "55") (name "MOTOR_6A") (class "Default")
      (node (ref "L13") (pin "1") (pinfunction "1_1") (pintype "unspecified"))
      (node (ref "U11") (pin "7") (pinfunction "BOUT1_7") (pintype "unspecified"))
    )
    (net (code "56") (name "MOTOR_6A_J") (class "Default")
      (node (ref "J7") (pin "1") (pinfunction "1_1") (pintype "unspecified"))
      (node (ref "L13") (pin "2") (pinfunction "2_2") (pintype "unspecified"))
      (node (ref "U22") (pin "1") (pinfunction "1_1") (pintype "unspecified"))
    )
    (net (code "57") (name "MOTOR_6B") (class "Default")
      (node (ref "L14") (pin "1") (pinfunction "1_1") (pintype "unspecified"))
      (node (ref "U11") (pin "5") (pinfunction "BOUT2_5") (pintype "unspecified"))
    )
    (net (code "58") (name "MOTOR_6B_J") (class "Default")
      (node (ref "J7") (pin "3") (pinfunction "3_3") (pintype "unspecified"))
      (node (ref "L14") (pin "2") (pinfunction "2_2") (pintype "unspecified"))
      (node (ref "U23") (pin "1") (pinfunction "1_1") (pintype "unspecified"))
    )
    (net (code "59") (name "MOTOR_ADDR0") (class "Default")
      (node (ref "R26") (pin "2") (pinfunction "2_2") (pintype "input"))
      (node (ref "U28") (pin "2") (pinfunction "A0_2") (pintype "input"))
      (node (ref "U6") (pin "20") (pinfunction "IO12_20") (pintype "unspecified"))
    )
    (net (code "60") (name "MOTOR_ADDR1") (class "Default")
      (node (ref "R27") (pin "2") (pinfunction "2_2") (pintype "input"))
      (node (ref "U28") (pin "3") (pinfunction "A1_3") (pintype "input"))
      (node (ref "U6") (pin "19") (pinfunction "IO11_19") (pintype "unspecified"))
    )
    (net (code "61") (name "MOTOR_ADDR2") (class "Default")
      (node (ref "R28") (pin "2") (pinfunction "2_2") (pintype "input"))
      (node (ref "U28") (pin "21") (pinfunction "A2_21") (pintype "input"))
      (node (ref "U6") (pin "22") (pinfunction "IO14_22") (pintype "unspecified"))
    )
    (net (code "62") (name "MOTOR_ADDR3") (class "Default")
      (node (ref "R29") (pin "2") (pinfunction "2_2") (pintype "input"))
      (node (ref "U28") (pin "22") (pinfunction "A3_22") (pintype "input"))
      (node (ref "U6") (pin "21") (pinfunction "IO13_21") (pintype "unspecified"))
    )
    (net (code "63") (name "MOTOR_ENABLE") (class "Default")
      (node (ref "R30") (pin "2") (pinfunction "2_2") (pintype "input"))
      (node (ref "U6") (pin "11") (pinfunction "IO18_11") (pintype "unspecified"))
      (node (ref "U7") (pin "1") (pinfunction "A_1") (pintype "input"))
    )
    (net (code "64") (name "ONEWIRE_BUS") (class "Default")
      (node (ref "J1") (pin "2") (pinfunction "2_2") (pintype "unspecified"))
      (node (ref "R20") (pin "1") (pinfunction "1_1") (pintype "input"))
      (node (ref "R21") (pin "1") (pinfunction "1_1") (pintype "input"))
      (node (ref "U30") (pin "2") (pinfunction "2_2") (pintype "unspecified"))
    )
    (net (code "65") (name "ONEWIRE_MCU") (class "Default")
      (node (ref "R20") (pin "2") (pinfunction "2_2") (pintype "input"))
      (node (ref "U6") (pin "12") (pinfunction "IO8_12") (pintype "unspecified"))
    )
    (net (code "66") (name "RAIL_OVERCURRENT") (class "Default")
      (node (ref "C43") (pin "1") (pinfunction "1_1") (pintype "input"))
      (node (ref "R41") (pin "1") (pinfunction "1_1") (pintype "input"))
      (node (ref "U3") (pin "1") (pinfunction "1OUT_1") (pintype "unspecified"))
      (node (ref "U6") (pin "25") (pinfunction "IO48_25") (pintype "unspecified"))
    )
    (net (code "67") (name "REV1") (class "Default")
      (node (ref "U28") (pin "5") (pinfunction "Q6_5") (pintype "input"))
      (node (ref "U9") (pin "15") (pinfunction "AIN2_15") (pintype "unspecified"))
    )
    (net (code "68") (name "REV2") (class "Default")
      (node (ref "U28") (pin "6") (pinfunction "Q5_6") (pintype "input"))
      (node (ref "U9") (pin "10") (pinfunction "BIN2_10") (pintype "unspecified"))
    )
    (net (code "69") (name "REV3") (class "Default")
      (node (ref "U10") (pin "15") (pinfunction "AIN2_15") (pintype "unspecified"))
      (node (ref "U28") (pin "14") (pinfunction "Q12_14") (pintype "input"))
    )
    (net (code "70") (name "REV4") (class "Default")
      (node (ref "U10") (pin "10") (pinfunction "BIN2_10") (pintype "unspecified"))
      (node (ref "U28") (pin "15") (pinfunction "Q15_15") (pintype "input"))
    )
    (net (code "71") (name "REV5") (class "Default")
      (node (ref "U11") (pin "15") (pinfunction "AIN2_15") (pintype "unspecified"))
      (node (ref "U28") (pin "18") (pinfunction "Q8_18") (pintype "input"))
    )
    (net (code "72") (name "REV6") (class "Default")
      (node (ref "U11") (pin "10") (pinfunction "BIN2_10") (pintype "unspecified"))
      (node (ref "U28") (pin "19") (pinfunction "Q11_19") (pintype "input"))
    )
    (net (code "73") (name "STATUS_LED_A") (class "Default")
      (node (ref "D3") (pin "1") (pinfunction "A_1") (pintype "unspecified"))
      (node (ref "R23") (pin "1") (pinfunction "1_1") (pintype "input"))
    )
    (net (code "74") (name "STATUS_LED_N") (class "Default")
      (node (ref "D3") (pin "2") (pinfunction "K_2") (pintype "unspecified"))
      (node (ref "U6") (pin "4") (pinfunction "IO4_4") (pintype "unspecified"))
    )
    (net (code "75") (name "TACHO_AC") (class "Default")
      (node (ref "C8") (pin "1") (pinfunction "1_1") (pintype "input"))
      (node (ref "R9") (pin "1") (pinfunction "1_1") (pintype "input"))
      (node (ref "U5") (pin "3") (pinfunction "IN+_3") (pintype "unspecified"))
    )
    (net (code "76") (name "TACHO_AMP") (class "Default")
      (node (ref "C10") (pin "2") (pinfunction "2_2") (pintype "input"))
      (node (ref "R10") (pin "1") (pinfunction "1_1") (pintype "input"))
      (node (ref "R13") (pin "1") (pinfunction "1_1") (pintype "input"))
      (node (ref "R14") (pin "1") (pinfunction "1_1") (pintype "input"))
      (node (ref "TP4") (pin "1") (pinfunction "1_1") (pintype "unspecified"))
      (node (ref "U5") (pin "1") (pinfunction "OUT_1") (pintype "unspecified"))
    )
    (net (code "77") (name "TACHO_CMP") (class "Default")
      (node (ref "R14") (pin "2") (pinfunction "2_2") (pintype "input"))
      (node (ref "R15") (pin "1") (pinfunction "1_1") (pintype "input"))
      (node (ref "U3") (pin "5") (pinfunction "2IN+_5") (pintype "unspecified"))
    )
    (net (code "78") (name "TACHO_FB") (class "Default")
      (node (ref "C10") (pin "1") (pinfunction "1_1") (pintype "input"))
      (node (ref "R10") (pin "2") (pinfunction "2_2") (pintype "input"))
      (node (ref "R8") (pin "2") (pinfunction "2_2") (pintype "input"))
      (node (ref "U5") (pin "4") (pinfunction "IN-_4") (pintype "unspecified"))
    )
    (net (code "79") (name "TACHO_REF") (class "Default")
      (node (ref "C9") (pin "2") (pinfunction "2_2") (pintype "unspecified"))
      (node (ref "R11") (pin "1") (pinfunction "1_1") (pintype "input"))
      (node (ref "R12") (pin "2") (pinfunction "2_2") (pintype "input"))
      (node (ref "R8") (pin "1") (pinfunction "1_1") (pintype "input"))
      (node (ref "R9") (pin "2") (pinfunction "2_2") (pintype "input"))
      (node (ref "U3") (pin "6") (pinfunction "2IN-_6") (pintype "unspecified"))
    )
    (net (code "80") (name "UART_RX") (class "Default")
      (node (ref "R40") (pin "1") (pinfunction "1_1") (pintype "input"))
      (node (ref "U6") (pin "36") (pinfunction "RXD0_36") (pintype "unspecified"))
    )
    (net (code "81") (name "UART_RX_DBG") (class "Default")
      (node (ref "J9") (pin "4") (pinfunction "4_4") (pintype "unspecified"))
      (node (ref "R40") (pin "2") (pinfunction "2_2") (pintype "input"))
    )
    (net (code "82") (name "UART_TX") (class "Default")
      (node (ref "R39") (pin "1") (pinfunction "1_1") (pintype "input"))
      (node (ref "U6") (pin "37") (pinfunction "TXD0_37") (pintype "unspecified"))
    )
    (net (code "83") (name "UART_TX_DBG") (class "Default")
      (node (ref "J9") (pin "3") (pinfunction "3_3") (pintype "unspecified"))
      (node (ref "R39") (pin "2") (pinfunction "2_2") (pintype "input"))
    )
    (net (code "84") (name "USB_CC1") (class "Default")
      (node (ref "R33") (pin "1") (pinfunction "1_1") (pintype "input"))
      (node (ref "USBC1") (pin "A5") (pinfunction "CC1_A5") (pintype "unspecified"))
    )
    (net (code "85") (name "USB_CC2") (class "Default")
      (node (ref "R32") (pin "1") (pinfunction "1_1") (pintype "input"))
      (node (ref "USBC1") (pin "B5") (pinfunction "CC2_B5") (pintype "unspecified"))
    )
    (net (code "86") (name "USB_DM") (class "Default")
      (node (ref "U27") (pin "6") (pinfunction "6_6") (pintype "input"))
      (node (ref "U6") (pin "13") (pinfunction "IO19_13") (pintype "unspecified"))
    )
    (net (code "87") (name "USB_DN_IN") (class "Default")
      (node (ref "U27") (pin "1") (pinfunction "1_1") (pintype "input"))
      (node (ref "USBC1") (pin "A7") (pinfunction "DN1_A7") (pintype "unspecified"))
      (node (ref "USBC1") (pin "B7") (pinfunction "DN2_B7") (pintype "unspecified"))
    )
    (net (code "88") (name "USB_DP") (class "Default")
      (node (ref "U27") (pin "4") (pinfunction "4_4") (pintype "input"))
      (node (ref "U6") (pin "14") (pinfunction "IO20_14") (pintype "unspecified"))
    )
    (net (code "89") (name "USB_DP_IN") (class "Default")
      (node (ref "U27") (pin "3") (pinfunction "3_3") (pintype "input"))
      (node (ref "USBC1") (pin "A6") (pinfunction "DP1_A6") (pintype "unspecified"))
      (node (ref "USBC1") (pin "B6") (pinfunction "DP2_B6") (pintype "unspecified"))
    )
    (net (code "90") (name "USB_ILIM") (class "Default")
      (node (ref "R34") (pin "1") (pinfunction "1_1") (pintype "input"))
      (node (ref "U24") (pin "5") (pinfunction "ILIM_5") (pintype "input"))
    )
    (net (code "91") (name "VBUS_PROTECTED") (class "Default")
      (node (ref "C11") (pin "1") (pinfunction "1_1") (pintype "unspecified"))
      (node (ref "C32") (pin "2") (pinfunction "2_2") (pintype "unspecified"))
      (node (ref "C33") (pin "2") (pinfunction "2_2") (pintype "unspecified"))
      (node (ref "C34") (pin "2") (pinfunction "2_2") (pintype "unspecified"))
      (node (ref "TP-VBUS_PROTECTED") (pin "1") (pinfunction "1_1") (pintype "unspecified"))
      (node (ref "U24") (pin "6") (pinfunction "OUT_6") (pintype "input"))
      (node (ref "U25") (pin "1") (pinfunction "EN_1") (pintype "unspecified"))
      (node (ref "U25") (pin "4") (pinfunction "IN_4") (pintype "unspecified"))
      (node (ref "U26") (pin "1") (pinfunction "VIN_1") (pintype "unspecified"))
      (node (ref "U26") (pin "3") (pinfunction "EN_3") (pintype "unspecified"))
      (node (ref "U3") (pin "8") (pinfunction "VCC+_8") (pintype "unspecified"))
    )
    (net (code "92") (name "VBUS_RAW") (class "Default")
      (node (ref "C31") (pin "2") (pinfunction "2_2") (pintype "input"))
      (node (ref "TP-VBUS_RAW") (pin "1") (pinfunction "1_1") (pintype "unspecified"))
      (node (ref "U24") (pin "1") (pinfunction "IN_1") (pintype "input"))
      (node (ref "U24") (pin "3") (pinfunction "EN_3") (pintype "input"))
      (node (ref "U27") (pin "5") (pinfunction "5_5") (pintype "input"))
      (node (ref "USBC1") (pin "A4B9") (pinfunction "VBUS_A4B9") (pintype "unspecified"))
      (node (ref "USBC1") (pin "B4A9") (pinfunction "VBUS_B4A9") (pintype "unspecified"))
    )
    (net (code "93") (name "unconnected-(J2-Pad2)") (class "Default")
      (node (ref "J2") (pin "2") (pinfunction "2_2") (pintype "unspecified+no_connect"))
    )
    (net (code "94") (name "unconnected-(J2-Pad4)") (class "Default")
      (node (ref "J2") (pin "4") (pinfunction "4_4") (pintype "unspecified+no_connect"))
    )
    (net (code "95") (name "unconnected-(J3-Pad2)") (class "Default")
      (node (ref "J3") (pin "2") (pinfunction "2_2") (pintype "unspecified+no_connect"))
    )
    (net (code "96") (name "unconnected-(J3-Pad4)") (class "Default")
      (node (ref "J3") (pin "4") (pinfunction "4_4") (pintype "unspecified+no_connect"))
    )
    (net (code "97") (name "unconnected-(J4-Pad2)") (class "Default")
      (node (ref "J4") (pin "2") (pinfunction "2_2") (pintype "unspecified+no_connect"))
    )
    (net (code "98") (name "unconnected-(J4-Pad4)") (class "Default")
      (node (ref "J4") (pin "4") (pinfunction "4_4") (pintype "unspecified+no_connect"))
    )
    (net (code "99") (name "unconnected-(J5-Pad2)") (class "Default")
      (node (ref "J5") (pin "2") (pinfunction "2_2") (pintype "unspecified+no_connect"))
    )
    (net (code "100") (name "unconnected-(J5-Pad4)") (class "Default")
      (node (ref "J5") (pin "4") (pinfunction "4_4") (pintype "unspecified+no_connect"))
    )
    (net (code "101") (name "unconnected-(J6-Pad2)") (class "Default")
      (node (ref "J6") (pin "2") (pinfunction "2_2") (pintype "unspecified+no_connect"))
    )
    (net (code "102") (name "unconnected-(J6-Pad4)") (class "Default")
      (node (ref "J6") (pin "4") (pinfunction "4_4") (pintype "unspecified+no_connect"))
    )
    (net (code "103") (name "unconnected-(J7-Pad2)") (class "Default")
      (node (ref "J7") (pin "2") (pinfunction "2_2") (pintype "unspecified+no_connect"))
    )
    (net (code "104") (name "unconnected-(J7-Pad4)") (class "Default")
      (node (ref "J7") (pin "4") (pinfunction "4_4") (pintype "unspecified+no_connect"))
    )
    (net (code "105") (name "unconnected-(U6-IO3-Pad15)") (class "Default")
      (node (ref "U6") (pin "15") (pinfunction "IO3_15") (pintype "unspecified+no_connect"))
    )
    (net (code "106") (name "unconnected-(U6-IO5-Pad5)") (class "Default")
      (node (ref "U6") (pin "5") (pinfunction "IO5_5") (pintype "unspecified+no_connect"))
    )
    (net (code "107") (name "unconnected-(U6-IO6-Pad6)") (class "Default")
      (node (ref "U6") (pin "6") (pinfunction "IO6_6") (pintype "unspecified+no_connect"))
    )
    (net (code "108") (name "unconnected-(U6-IO7-Pad7)") (class "Default")
      (node (ref "U6") (pin "7") (pinfunction "IO7_7") (pintype "unspecified+no_connect"))
    )
    (net (code "109") (name "unconnected-(U6-IO9-Pad17)") (class "Default")
      (node (ref "U6") (pin "17") (pinfunction "IO9_17") (pintype "unspecified+no_connect"))
    )
    (net (code "110") (name "unconnected-(U6-IO10-Pad18)") (class "Default")
      (node (ref "U6") (pin "18") (pinfunction "IO10_18") (pintype "unspecified+no_connect"))
    )
    (net (code "111") (name "unconnected-(U6-IO35-Pad28)") (class "Default")
      (node (ref "U6") (pin "28") (pinfunction "IO35_28") (pintype "unspecified+no_connect"))
    )
    (net (code "112") (name "unconnected-(U6-IO36-Pad29)") (class "Default")
      (node (ref "U6") (pin "29") (pinfunction "IO36_29") (pintype "unspecified+no_connect"))
    )
    (net (code "113") (name "unconnected-(U6-IO37-Pad30)") (class "Default")
      (node (ref "U6") (pin "30") (pinfunction "IO37_30") (pintype "unspecified+no_connect"))
    )
    (net (code "114") (name "unconnected-(U6-IO39-Pad32)") (class "Default")
      (node (ref "U6") (pin "32") (pinfunction "IO39_32") (pintype "unspecified+no_connect"))
    )
    (net (code "115") (name "unconnected-(U6-IO40-Pad33)") (class "Default")
      (node (ref "U6") (pin "33") (pinfunction "IO40_33") (pintype "unspecified+no_connect"))
    )
    (net (code "116") (name "unconnected-(U6-IO41-Pad34)") (class "Default")
      (node (ref "U6") (pin "34") (pinfunction "IO41_34") (pintype "unspecified+no_connect"))
    )
    (net (code "117") (name "unconnected-(U6-IO42-Pad35)") (class "Default")
      (node (ref "U6") (pin "35") (pinfunction "IO42_35") (pintype "unspecified+no_connect"))
    )
    (net (code "118") (name "unconnected-(U6-IO45-Pad26)") (class "Default")
      (node (ref "U6") (pin "26") (pinfunction "IO45_26") (pintype "unspecified+no_connect"))
    )
    (net (code "119") (name "unconnected-(U6-IO46-Pad16)") (class "Default")
      (node (ref "U6") (pin "16") (pinfunction "IO46_16") (pintype "unspecified+no_connect"))
    )
    (net (code "120") (name "unconnected-(U9-NC-Pad11)") (class "Default")
      (node (ref "U9") (pin "11") (pinfunction "NC_11") (pintype "unspecified+no_connect"))
    )
    (net (code "121") (name "unconnected-(U9-NC-Pad14)") (class "Default")
      (node (ref "U9") (pin "14") (pinfunction "NC_14") (pintype "unspecified+no_connect"))
    )
    (net (code "122") (name "unconnected-(U10-NC-Pad11)") (class "Default")
      (node (ref "U10") (pin "11") (pinfunction "NC_11") (pintype "unspecified+no_connect"))
    )
    (net (code "123") (name "unconnected-(U10-NC-Pad14)") (class "Default")
      (node (ref "U10") (pin "14") (pinfunction "NC_14") (pintype "unspecified+no_connect"))
    )
    (net (code "124") (name "unconnected-(U11-NC-Pad11)") (class "Default")
      (node (ref "U11") (pin "11") (pinfunction "NC_11") (pintype "unspecified+no_connect"))
    )
    (net (code "125") (name "unconnected-(U11-NC-Pad14)") (class "Default")
      (node (ref "U11") (pin "14") (pinfunction "NC_14") (pintype "unspecified+no_connect"))
    )
    (net (code "126") (name "unconnected-(U26-NC-Pad4)") (class "Default")
      (node (ref "U26") (pin "4") (pinfunction "NC_4") (pintype "unspecified+no_connect"))
    )
    (net (code "127") (name "unconnected-(U28-Q0-Pad11)") (class "Default")
      (node (ref "U28") (pin "11") (pinfunction "Q0_11") (pintype "input+no_connect"))
    )
    (net (code "128") (name "unconnected-(U28-Q1-Pad9)") (class "Default")
      (node (ref "U28") (pin "9") (pinfunction "Q1_9") (pintype "input+no_connect"))
    )
    (net (code "129") (name "unconnected-(U28-Q2-Pad10)") (class "Default")
      (node (ref "U28") (pin "10") (pinfunction "Q2_10") (pintype "input+no_connect"))
    )
    (net (code "130") (name "unconnected-(U28-Q3-Pad8)") (class "Default")
      (node (ref "U28") (pin "8") (pinfunction "Q3_8") (pintype "input+no_connect"))
    )
    (net (code "131") (name "unconnected-(USBC1-SBU1-PadA8)") (class "Default")
      (node (ref "USBC1") (pin "A8") (pinfunction "SBU1_A8") (pintype "unspecified+no_connect"))
    )
    (net (code "132") (name "unconnected-(USBC1-SBU2-PadB8)") (class "Default")
      (node (ref "USBC1") (pin "B8") (pinfunction "SBU2_B8") (pintype "unspecified+no_connect"))
    )
  )
)
